# GeniusBottom.net
KiCad netlist of a schematic drawn in EAGLE
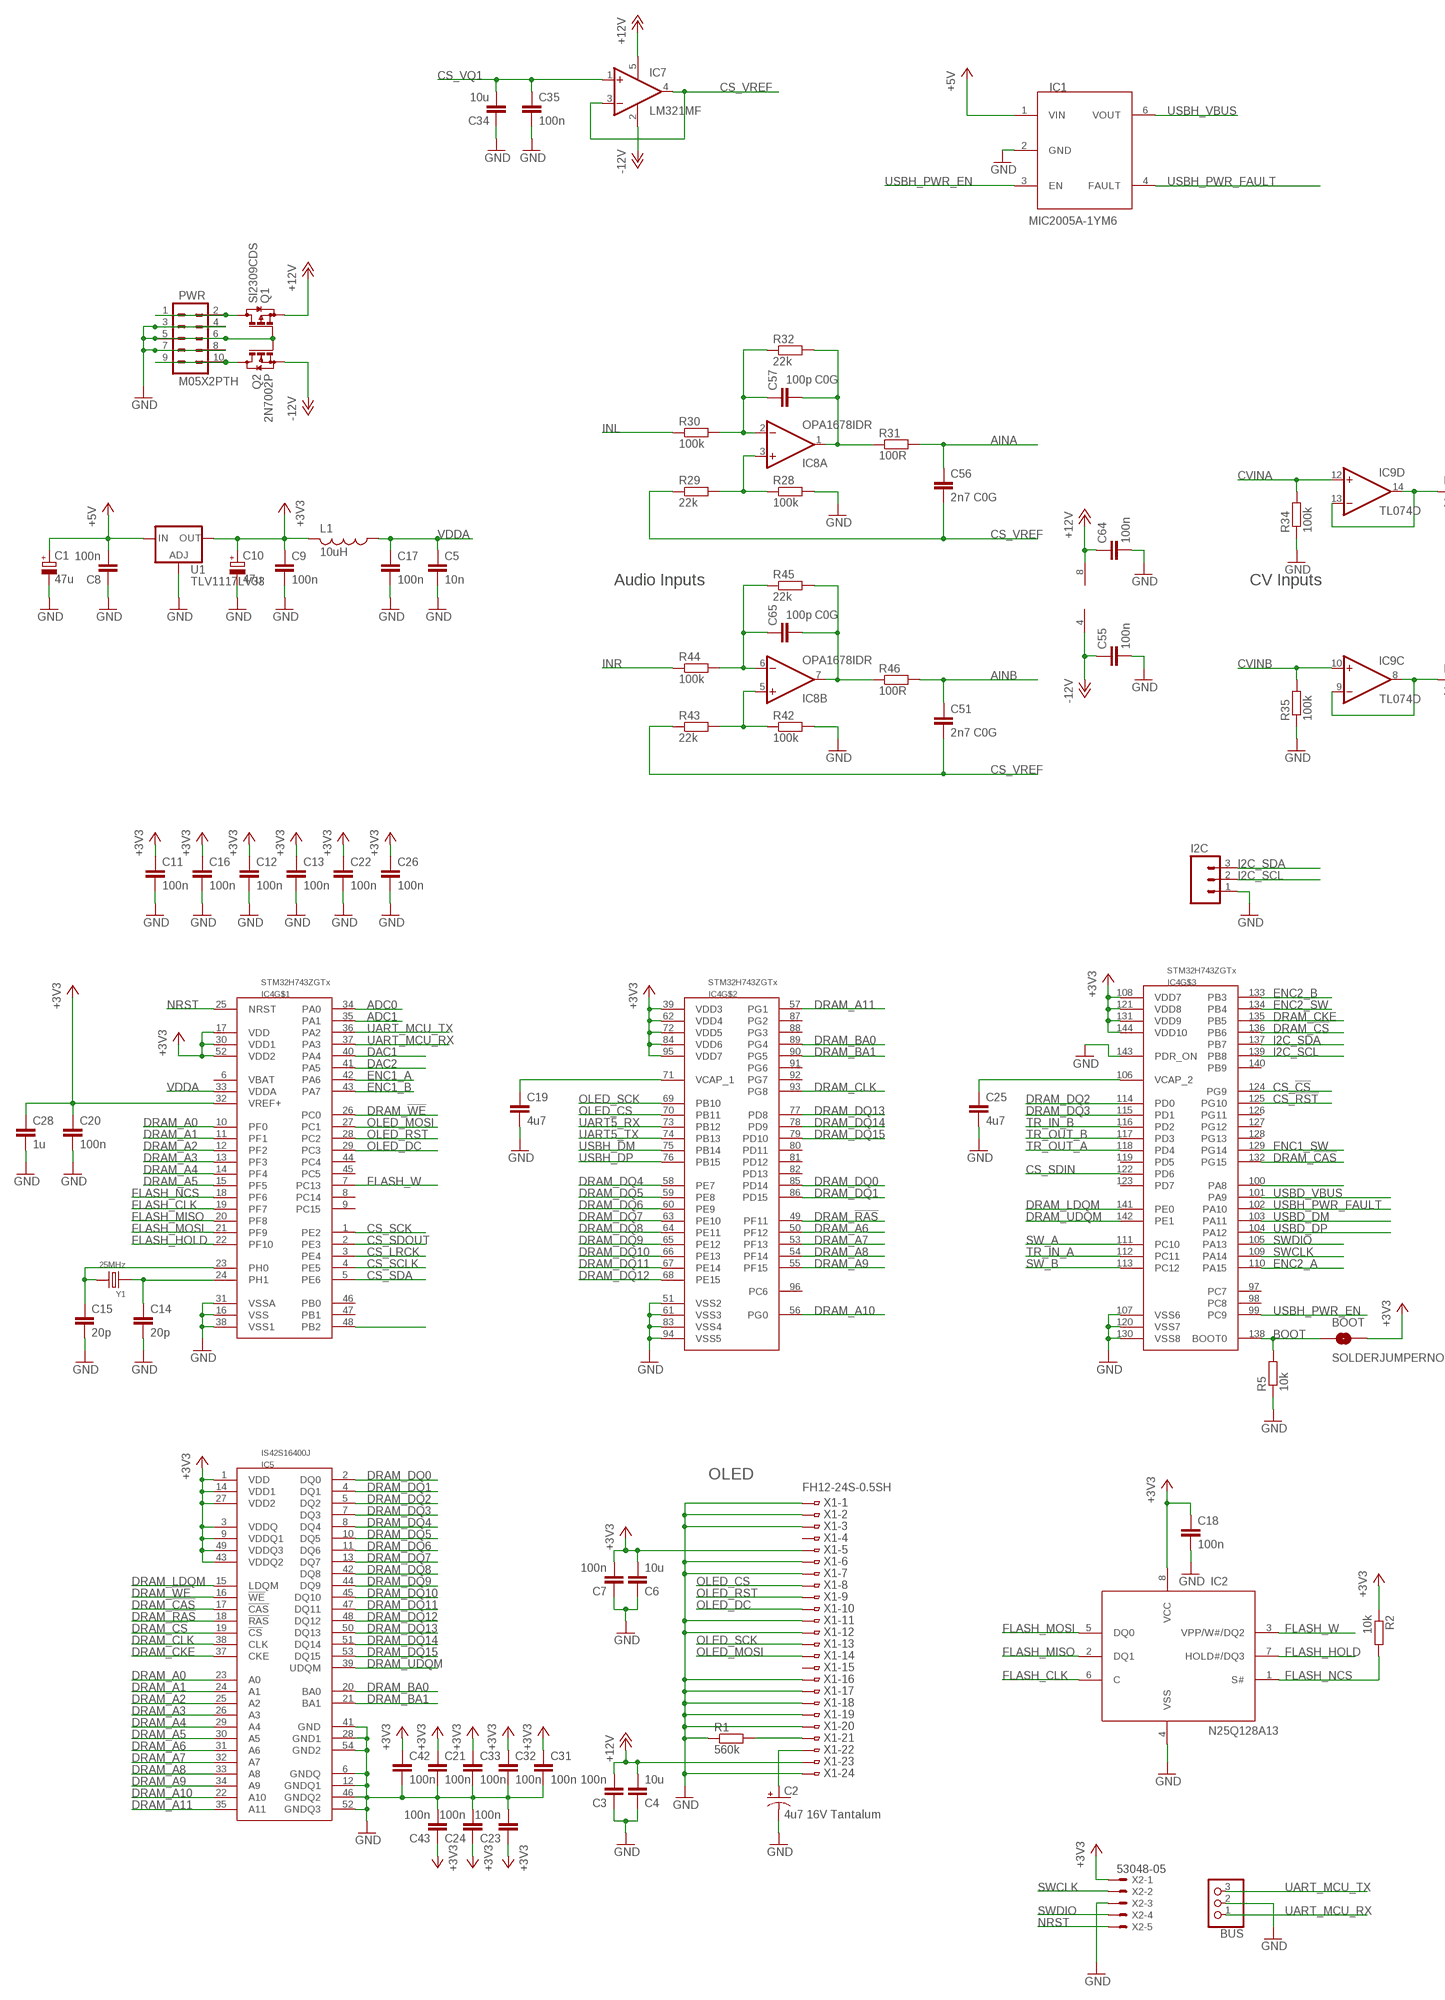
[diagram p0: schematic, sheet 1, part 1 of 2]
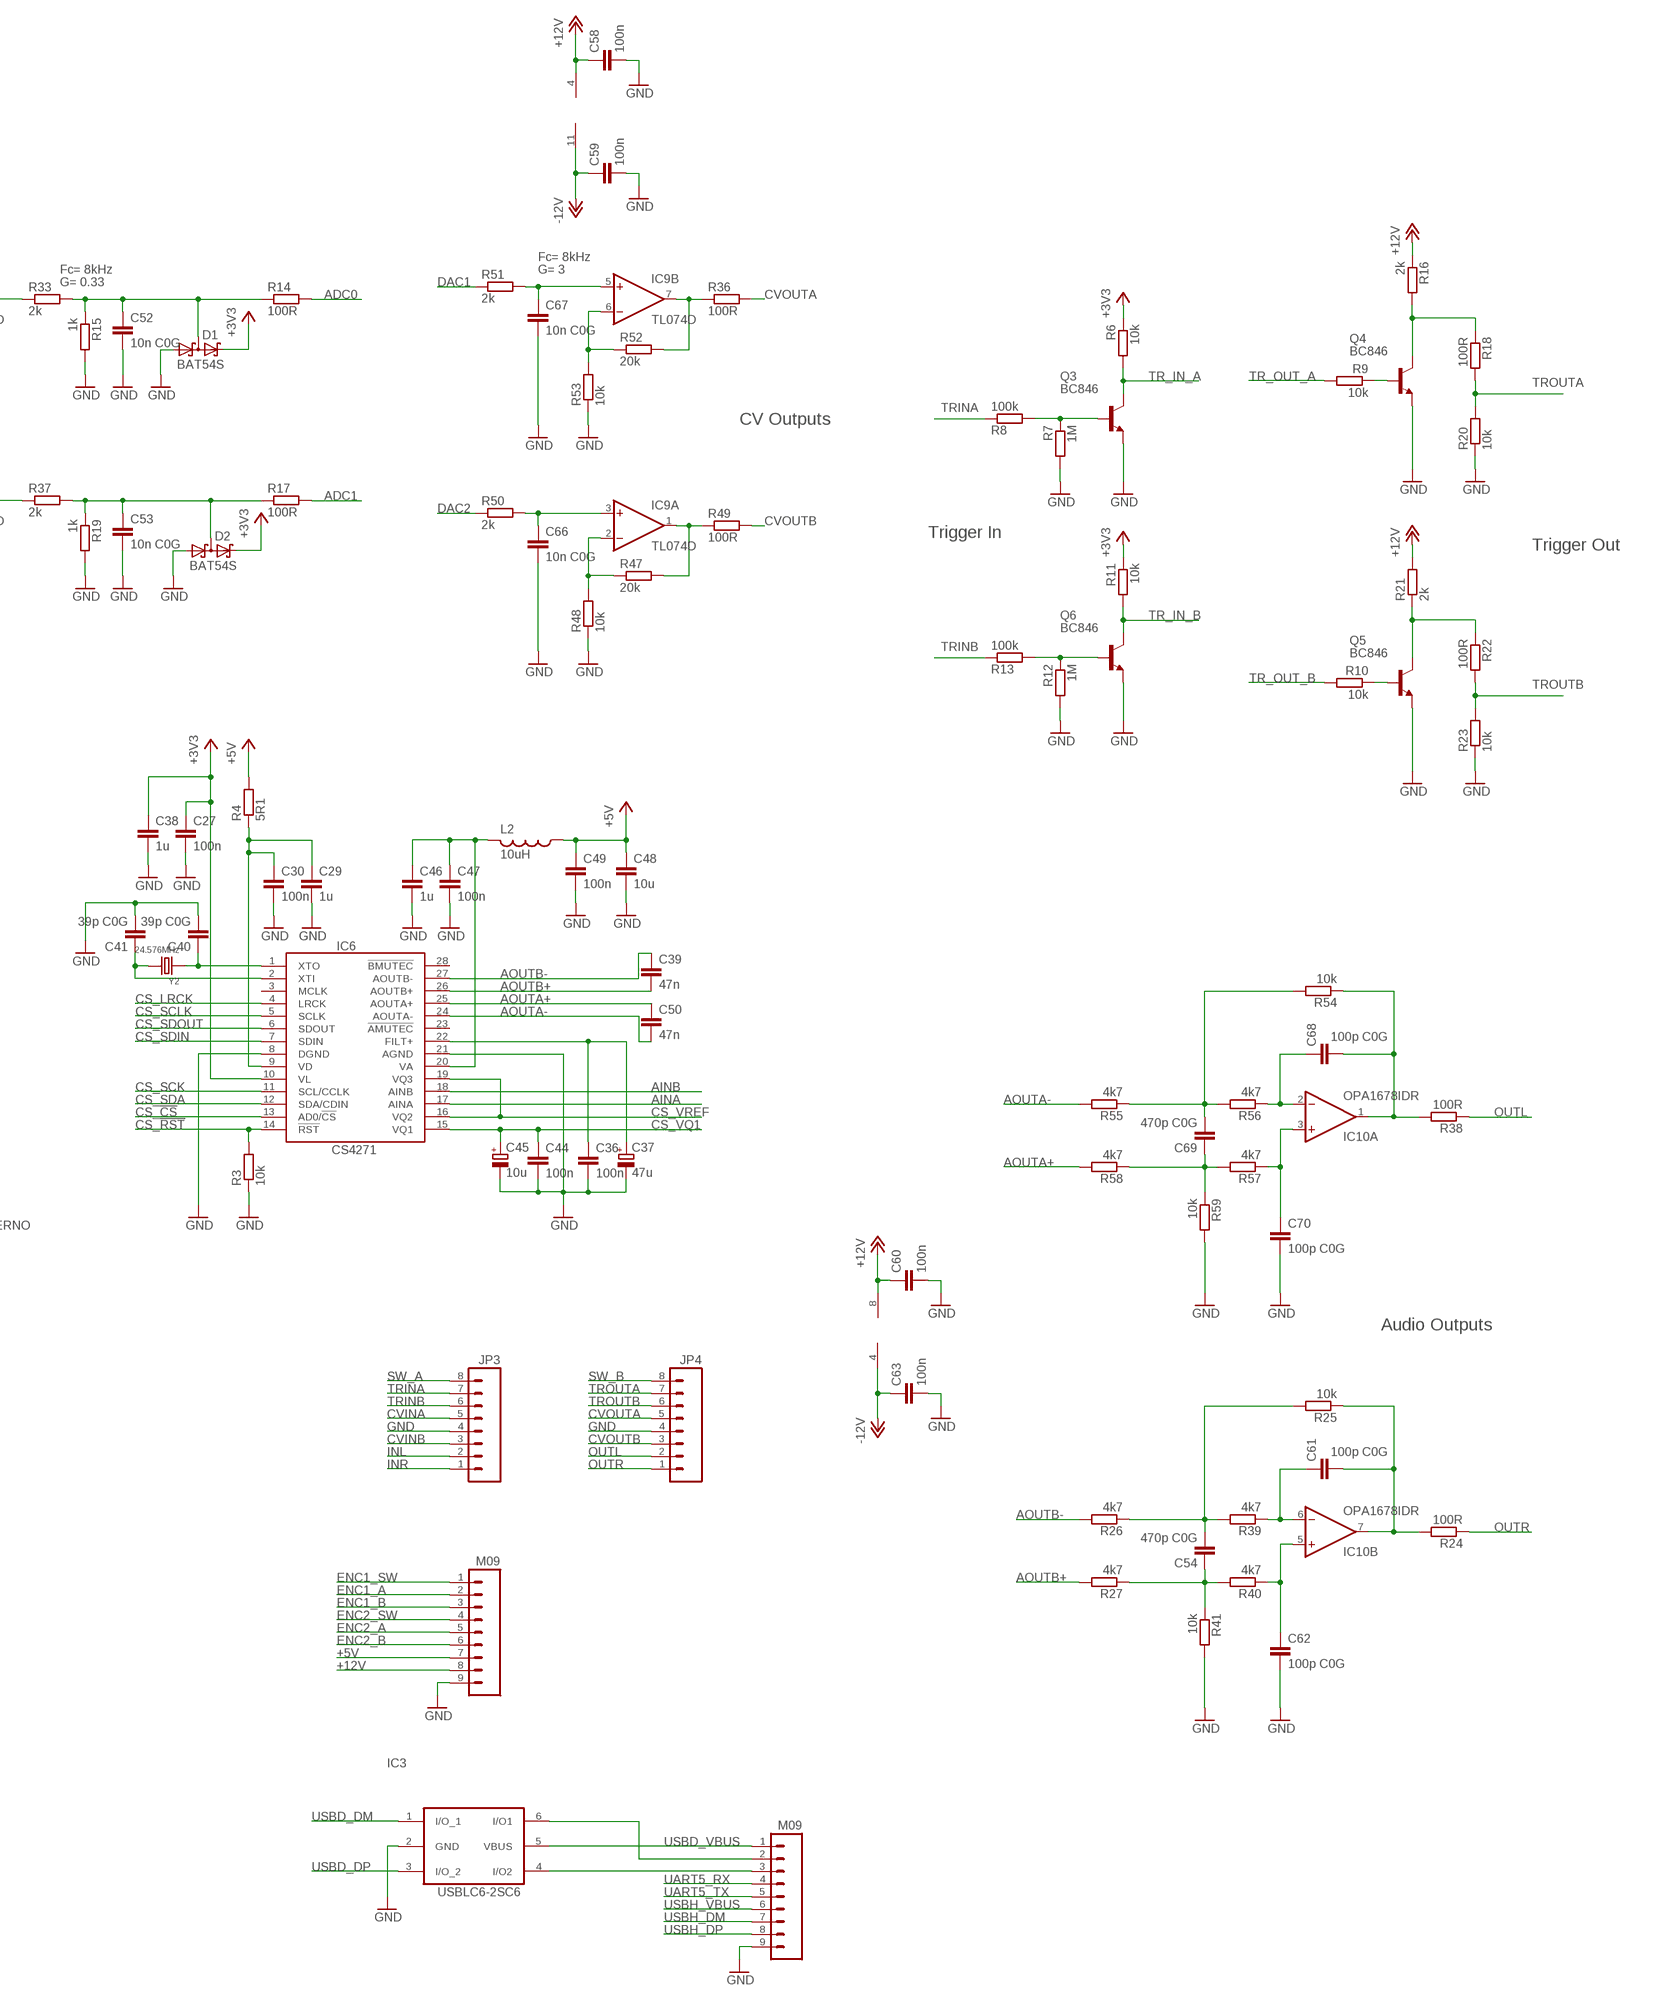
[diagram p1: schematic, sheet 1, part 2 of 2]

(export (version "E")
  (design (tool "Eeschema 10.0.6"))
  (components
    (comp (ref "BOOT")
      (value "SOLDERJUMPERNO")
      (footprint "eagle-import:SJ_2S-NO")
      (libsource (lib "eagle-import") (part "SOLDERJUMPERNO"))
    )
    (comp (ref "BUS")
      (value "CON-JST-1X03PH-TH")
      (footprint "eagle-import:JST-B3B-PH-KL")
      (libsource (lib "eagle-import") (part "CON-JST-1X03PH-TH"))
    )
    (comp (ref "C1")
      (value "47u")
      (footprint "eagle-import:CPOL-5")
      (libsource (lib "eagle-import") (part "CPOL-EU153CLV-0505"))
    )
    (comp (ref "C2")
      (value "4u7 16V Tantalum")
      (footprint "eagle-import:EIA3216")
      (libsource (lib "eagle-import") (part "CAP_POL1206"))
    )
    (comp (ref "C3")
      (value "100n")
      (footprint "eagle-import:C0603")
      (libsource (lib "eagle-import") (part "C-EUC0603"))
    )
    (comp (ref "C4")
      (value "10u")
      (footprint "eagle-import:C1206")
      (libsource (lib "eagle-import") (part "C-EUC1206"))
    )
    (comp (ref "C5")
      (value "10n")
      (footprint "eagle-import:C0603")
      (libsource (lib "eagle-import") (part "C-EUC0603"))
    )
    (comp (ref "C6")
      (value "10u")
      (footprint "eagle-import:C1206")
      (libsource (lib "eagle-import") (part "C-EUC1206"))
    )
    (comp (ref "C7")
      (value "100n")
      (footprint "eagle-import:C0603")
      (libsource (lib "eagle-import") (part "C-EUC0603"))
    )
    (comp (ref "C8")
      (value "100n")
      (footprint "eagle-import:C0603")
      (libsource (lib "eagle-import") (part "C-EUC0603"))
    )
    (comp (ref "C9")
      (value "100n")
      (footprint "eagle-import:C0603")
      (libsource (lib "eagle-import") (part "C-EUC0603"))
    )
    (comp (ref "C10")
      (value "47u")
      (footprint "eagle-import:CPOL-5")
      (libsource (lib "eagle-import") (part "CPOL-EU153CLV-0505"))
    )
    (comp (ref "C11")
      (value "100n")
      (footprint "eagle-import:C0603")
      (libsource (lib "eagle-import") (part "C-EUC0603"))
    )
    (comp (ref "C12")
      (value "100n")
      (footprint "eagle-import:C0603")
      (libsource (lib "eagle-import") (part "C-EUC0603"))
    )
    (comp (ref "C13")
      (value "100n")
      (footprint "eagle-import:C0603")
      (libsource (lib "eagle-import") (part "C-EUC0603"))
    )
    (comp (ref "C14")
      (value "20p")
      (footprint "eagle-import:C0603")
      (libsource (lib "eagle-import") (part "C-EUC0603"))
    )
    (comp (ref "C15")
      (value "20p")
      (footprint "eagle-import:C0603")
      (libsource (lib "eagle-import") (part "C-EUC0603"))
    )
    (comp (ref "C16")
      (value "100n")
      (footprint "eagle-import:C0603")
      (libsource (lib "eagle-import") (part "C-EUC0603"))
    )
    (comp (ref "C17")
      (value "100n")
      (footprint "eagle-import:C0603")
      (libsource (lib "eagle-import") (part "C-EUC0603"))
    )
    (comp (ref "C18")
      (value "100n")
      (footprint "eagle-import:C0603")
      (libsource (lib "eagle-import") (part "C-EUC0603"))
    )
    (comp (ref "C19")
      (value "4u7")
      (footprint "eagle-import:C0603")
      (libsource (lib "eagle-import") (part "C-EUC0603"))
    )
    (comp (ref "C20")
      (value "100n")
      (footprint "eagle-import:C0603")
      (libsource (lib "eagle-import") (part "C-EUC0603"))
    )
    (comp (ref "C21")
      (value "100n")
      (footprint "eagle-import:C0603")
      (libsource (lib "eagle-import") (part "C-EUC0603"))
    )
    (comp (ref "C22")
      (value "100n")
      (footprint "eagle-import:C0603")
      (libsource (lib "eagle-import") (part "C-EUC0603"))
    )
    (comp (ref "C23")
      (value "100n")
      (footprint "eagle-import:C0603")
      (libsource (lib "eagle-import") (part "C-EUC0603"))
    )
    (comp (ref "C24")
      (value "100n")
      (footprint "eagle-import:C0603")
      (libsource (lib "eagle-import") (part "C-EUC0603"))
    )
    (comp (ref "C25")
      (value "4u7")
      (footprint "eagle-import:C0603")
      (libsource (lib "eagle-import") (part "C-EUC0603"))
    )
    (comp (ref "C26")
      (value "100n")
      (footprint "eagle-import:C0603")
      (libsource (lib "eagle-import") (part "C-EUC0603"))
    )
    (comp (ref "C27")
      (value "100n")
      (footprint "eagle-import:C0603")
      (libsource (lib "eagle-import") (part "C-EUC0603"))
    )
    (comp (ref "C28")
      (value "1u")
      (footprint "eagle-import:C0603")
      (libsource (lib "eagle-import") (part "C-EUC0603"))
    )
    (comp (ref "C29")
      (value "1u")
      (footprint "eagle-import:C0603")
      (libsource (lib "eagle-import") (part "C-EUC0603"))
    )
    (comp (ref "C30")
      (value "100n")
      (footprint "eagle-import:C0603")
      (libsource (lib "eagle-import") (part "C-EUC0603"))
    )
    (comp (ref "C31")
      (value "100n")
      (footprint "eagle-import:C0603")
      (libsource (lib "eagle-import") (part "C-EUC0603"))
    )
    (comp (ref "C32")
      (value "100n")
      (footprint "eagle-import:C0603")
      (libsource (lib "eagle-import") (part "C-EUC0603"))
    )
    (comp (ref "C33")
      (value "100n")
      (footprint "eagle-import:C0603")
      (libsource (lib "eagle-import") (part "C-EUC0603"))
    )
    (comp (ref "C34")
      (value "10u")
      (footprint "eagle-import:C1206")
      (libsource (lib "eagle-import") (part "C-EUC1206"))
    )
    (comp (ref "C35")
      (value "100n")
      (footprint "eagle-import:C0603")
      (libsource (lib "eagle-import") (part "C-EUC0603"))
    )
    (comp (ref "C36")
      (value "100n")
      (footprint "eagle-import:C0603")
      (libsource (lib "eagle-import") (part "C-EUC0603"))
    )
    (comp (ref "C37")
      (value "47u")
      (footprint "eagle-import:CPOL-5")
      (libsource (lib "eagle-import") (part "CPOL-EU153CLV-0505"))
    )
    (comp (ref "C38")
      (value "1u")
      (footprint "eagle-import:C0603")
      (libsource (lib "eagle-import") (part "C-EUC0603"))
    )
    (comp (ref "C39")
      (value "47n")
      (footprint "eagle-import:C0603")
      (libsource (lib "eagle-import") (part "C-EUC0603"))
    )
    (comp (ref "C40")
      (value "39p C0G")
      (footprint "eagle-import:C0603")
      (libsource (lib "eagle-import") (part "C-EUC0603"))
    )
    (comp (ref "C41")
      (value "39p C0G")
      (footprint "eagle-import:C0603")
      (libsource (lib "eagle-import") (part "C-EUC0603"))
    )
    (comp (ref "C42")
      (value "100n")
      (footprint "eagle-import:C0603")
      (libsource (lib "eagle-import") (part "C-EUC0603"))
    )
    (comp (ref "C43")
      (value "100n")
      (footprint "eagle-import:C0603")
      (libsource (lib "eagle-import") (part "C-EUC0603"))
    )
    (comp (ref "C44")
      (value "100n")
      (footprint "eagle-import:C0603")
      (libsource (lib "eagle-import") (part "C-EUC0603"))
    )
    (comp (ref "C45")
      (value "10u")
      (footprint "eagle-import:CPOL-5")
      (libsource (lib "eagle-import") (part "CPOL-EU153CLV-0505"))
    )
    (comp (ref "C46")
      (value "1u")
      (footprint "eagle-import:C0603")
      (libsource (lib "eagle-import") (part "C-EUC0603"))
    )
    (comp (ref "C47")
      (value "100n")
      (footprint "eagle-import:C0603")
      (libsource (lib "eagle-import") (part "C-EUC0603"))
    )
    (comp (ref "C48")
      (value "10u")
      (footprint "eagle-import:C1206")
      (libsource (lib "eagle-import") (part "C-EUC1206"))
    )
    (comp (ref "C49")
      (value "100n")
      (footprint "eagle-import:C0603")
      (libsource (lib "eagle-import") (part "C-EUC0603"))
    )
    (comp (ref "C50")
      (value "47n")
      (footprint "eagle-import:C0603")
      (libsource (lib "eagle-import") (part "C-EUC0603"))
    )
    (comp (ref "C51")
      (value "2n7 C0G")
      (footprint "eagle-import:C0603")
      (libsource (lib "eagle-import") (part "C-EUC0603"))
    )
    (comp (ref "C52")
      (value "10n C0G")
      (footprint "eagle-import:C0603")
      (libsource (lib "eagle-import") (part "C-EUC0603"))
    )
    (comp (ref "C53")
      (value "10n C0G")
      (footprint "eagle-import:C0603")
      (libsource (lib "eagle-import") (part "C-EUC0603"))
    )
    (comp (ref "C54")
      (value "470p C0G")
      (footprint "eagle-import:C0603")
      (libsource (lib "eagle-import") (part "C-EUC0603"))
    )
    (comp (ref "C55")
      (value "100n")
      (footprint "eagle-import:C0603")
      (libsource (lib "eagle-import") (part "C-EUC0603"))
    )
    (comp (ref "C56")
      (value "2n7 C0G")
      (footprint "eagle-import:C0603")
      (libsource (lib "eagle-import") (part "C-EUC0603"))
    )
    (comp (ref "C57")
      (value "100p C0G")
      (footprint "eagle-import:C0603")
      (libsource (lib "eagle-import") (part "C-EUC0603"))
    )
    (comp (ref "C58")
      (value "100n")
      (footprint "eagle-import:C0603")
      (libsource (lib "eagle-import") (part "C-EUC0603"))
    )
    (comp (ref "C59")
      (value "100n")
      (footprint "eagle-import:C0603")
      (libsource (lib "eagle-import") (part "C-EUC0603"))
    )
    (comp (ref "C60")
      (value "100n")
      (footprint "eagle-import:C0603")
      (libsource (lib "eagle-import") (part "C-EUC0603"))
    )
    (comp (ref "C61")
      (value "100p C0G")
      (footprint "eagle-import:C0603")
      (libsource (lib "eagle-import") (part "C-EUC0603"))
    )
    (comp (ref "C62")
      (value "100p C0G")
      (footprint "eagle-import:C0603")
      (libsource (lib "eagle-import") (part "C-EUC0603"))
    )
    (comp (ref "C63")
      (value "100n")
      (footprint "eagle-import:C0603")
      (libsource (lib "eagle-import") (part "C-EUC0603"))
    )
    (comp (ref "C64")
      (value "100n")
      (footprint "eagle-import:C0603")
      (libsource (lib "eagle-import") (part "C-EUC0603"))
    )
    (comp (ref "C65")
      (value "100p C0G")
      (footprint "eagle-import:C0603")
      (libsource (lib "eagle-import") (part "C-EUC0603"))
    )
    (comp (ref "C66")
      (value "10n C0G")
      (footprint "eagle-import:C0603")
      (libsource (lib "eagle-import") (part "C-EUC0603"))
    )
    (comp (ref "C67")
      (value "10n C0G")
      (footprint "eagle-import:C0603")
      (libsource (lib "eagle-import") (part "C-EUC0603"))
    )
    (comp (ref "C68")
      (value "100p C0G")
      (footprint "eagle-import:C0603")
      (libsource (lib "eagle-import") (part "C-EUC0603"))
    )
    (comp (ref "C69")
      (value "470p C0G")
      (footprint "eagle-import:C0603")
      (libsource (lib "eagle-import") (part "C-EUC0603"))
    )
    (comp (ref "C70")
      (value "100p C0G")
      (footprint "eagle-import:C0603")
      (libsource (lib "eagle-import") (part "C-EUC0603"))
    )
    (comp (ref "D1")
      (value "BAT54S")
      (footprint "eagle-import:SOT23")
      (libsource (lib "eagle-import") (part "BAT54S"))
    )
    (comp (ref "D2")
      (value "BAT54S")
      (footprint "eagle-import:SOT23")
      (libsource (lib "eagle-import") (part "BAT54S"))
    )
    (comp (ref "I2C")
      (value "M03PTH")
      (footprint "eagle-import:1X03")
      (libsource (lib "eagle-import") (part "M03PTH"))
    )
    (comp (ref "IC1")
      (value "MIC2005A-1YM6")
      (footprint "eagle-import:SOT23-6")
      (libsource (lib "eagle-import") (part "MIC2005"))
    )
    (comp (ref "IC2")
      (value "N25Q128A13")
      (footprint "eagle-import:SO8W")
      (libsource (lib "eagle-import") (part "N25Q128A13"))
    )
    (comp (ref "IC3")
      (value "USBLC6-2SC6")
      (footprint "eagle-import:SOT-23-6L")
      (libsource (lib "eagle-import") (part "USBLC6-2SC6"))
    )
    (comp (ref "IC4")
      (value "STM32H743ZGTx")
      (footprint "eagle-import:QFP50P2200X2200X160-144N")
      (fields (field (name "OC_FARNELL") "2484975"))
      (libsource (lib "eagle-import") (part "STM32F42XZ/43XZ(144PIN)LQFP144"))
    )
    (comp (ref "IC5")
      (value "IS42S16400J")
      (footprint "eagle-import:TSOP54-400")
      (libsource (lib "eagle-import") (part "IS42S16400J"))
    )
    (comp (ref "IC6")
      (value "CS4271")
      (footprint "eagle-import:TSSOP28-0.65-9.7X4.4MM")
      (libsource (lib "eagle-import") (part "CS4271"))
    )
    (comp (ref "IC7")
      (value "LM321MF")
      (footprint "eagle-import:SOT23-5")
      (libsource (lib "eagle-import") (part "LM321?MF"))
    )
    (comp (ref "IC8")
      (value "OPA1678IDR")
      (footprint "eagle-import:SO08")
      (libsource (lib "eagle-import") (part "NE5532D"))
    )
    (comp (ref "IC9")
      (value "TL074D")
      (footprint "eagle-import:SO14")
      (libsource (lib "eagle-import") (part "TL074D"))
    )
    (comp (ref "IC10")
      (value "OPA1678IDR")
      (footprint "eagle-import:SO08")
      (libsource (lib "eagle-import") (part "NE5532D"))
    )
    (comp (ref "JP1")
      (value "M09")
      (footprint "eagle-import:1X09")
      (libsource (lib "eagle-import") (part "M09"))
    )
    (comp (ref "JP2")
      (value "M09")
      (footprint "eagle-import:1X09")
      (libsource (lib "eagle-import") (part "M09"))
    )
    (comp (ref "JP3")
      (value "M081X08")
      (footprint "eagle-import:1X08")
      (libsource (lib "eagle-import") (part "M081X08"))
    )
    (comp (ref "JP4")
      (value "M081X08")
      (footprint "eagle-import:1X08")
      (libsource (lib "eagle-import") (part "M081X08"))
    )
    (comp (ref "L1")
      (value "10uH")
      (footprint "eagle-import:0603")
      (libsource (lib "eagle-import") (part "INDUCTOR"))
    )
    (comp (ref "L2")
      (value "10uH")
      (footprint "eagle-import:0603")
      (libsource (lib "eagle-import") (part "INDUCTOR"))
    )
    (comp (ref "PWR")
      (value "M05X2PTH")
      (footprint "eagle-import:AVR_ICSP")
      (libsource (lib "eagle-import") (part "M05X2PTH"))
    )
    (comp (ref "Q1")
      (value "SI2309CDS")
      (footprint "eagle-import:SOT23")
      (libsource (lib "eagle-import") (part "BSS84"))
    )
    (comp (ref "Q2")
      (value "2N7002P")
      (footprint "eagle-import:SOT23")
      (libsource (lib "eagle-import") (part "BSS123"))
    )
    (comp (ref "Q3")
      (value "BC846")
      (footprint "eagle-import:SOT23")
      (libsource (lib "eagle-import") (part "BC846"))
    )
    (comp (ref "Q4")
      (value "BC846")
      (footprint "eagle-import:SOT23")
      (libsource (lib "eagle-import") (part "BC846"))
    )
    (comp (ref "Q5")
      (value "BC846")
      (footprint "eagle-import:SOT23")
      (libsource (lib "eagle-import") (part "BC846"))
    )
    (comp (ref "Q6")
      (value "BC846")
      (footprint "eagle-import:SOT23")
      (libsource (lib "eagle-import") (part "BC846"))
    )
    (comp (ref "R1")
      (value "560k")
      (footprint "eagle-import:0603")
      (libsource (lib "eagle-import") (part "R-EU_0603"))
    )
    (comp (ref "R2")
      (value "10k")
      (footprint "eagle-import:0603")
      (libsource (lib "eagle-import") (part "R-EU_0603"))
    )
    (comp (ref "R3")
      (value "10k")
      (footprint "eagle-import:0603")
      (libsource (lib "eagle-import") (part "R-EU_0603"))
    )
    (comp (ref "R4")
      (value "5R1")
      (footprint "eagle-import:0603")
      (libsource (lib "eagle-import") (part "R-EU_0603"))
    )
    (comp (ref "R5")
      (value "10k")
      (footprint "eagle-import:0603")
      (libsource (lib "eagle-import") (part "R-EU_0603"))
    )
    (comp (ref "R6")
      (value "10k")
      (footprint "eagle-import:0603")
      (libsource (lib "eagle-import") (part "R-EU_0603"))
    )
    (comp (ref "R7")
      (value "1M")
      (footprint "eagle-import:0603")
      (libsource (lib "eagle-import") (part "R-EU_0603"))
    )
    (comp (ref "R8")
      (value "100k")
      (footprint "eagle-import:0603")
      (libsource (lib "eagle-import") (part "R-EU_0603"))
    )
    (comp (ref "R9")
      (value "10k")
      (footprint "eagle-import:0603")
      (libsource (lib "eagle-import") (part "R-EU_0603"))
    )
    (comp (ref "R10")
      (value "10k")
      (footprint "eagle-import:0603")
      (libsource (lib "eagle-import") (part "R-EU_0603"))
    )
    (comp (ref "R11")
      (value "10k")
      (footprint "eagle-import:0603")
      (libsource (lib "eagle-import") (part "R-EU_0603"))
    )
    (comp (ref "R12")
      (value "1M")
      (footprint "eagle-import:0603")
      (libsource (lib "eagle-import") (part "R-EU_0603"))
    )
    (comp (ref "R13")
      (value "100k")
      (footprint "eagle-import:0603")
      (libsource (lib "eagle-import") (part "R-EU_0603"))
    )
    (comp (ref "R14")
      (value "100R")
      (footprint "eagle-import:0603")
      (libsource (lib "eagle-import") (part "R-EU_0603"))
    )
    (comp (ref "R15")
      (value "1k")
      (footprint "eagle-import:0603")
      (libsource (lib "eagle-import") (part "R-EU_0603"))
    )
    (comp (ref "R16")
      (value "2k")
      (footprint "eagle-import:0603")
      (libsource (lib "eagle-import") (part "R-EU_0603"))
    )
    (comp (ref "R17")
      (value "100R")
      (footprint "eagle-import:0603")
      (libsource (lib "eagle-import") (part "R-EU_0603"))
    )
    (comp (ref "R18")
      (value "100R")
      (footprint "eagle-import:0603")
      (libsource (lib "eagle-import") (part "R-EU_0603"))
    )
    (comp (ref "R19")
      (value "1k")
      (footprint "eagle-import:0603")
      (libsource (lib "eagle-import") (part "R-EU_0603"))
    )
    (comp (ref "R20")
      (value "10k")
      (footprint "eagle-import:0603")
      (libsource (lib "eagle-import") (part "R-EU_0603"))
    )
    (comp (ref "R21")
      (value "2k")
      (footprint "eagle-import:0603")
      (libsource (lib "eagle-import") (part "R-EU_0603"))
    )
    (comp (ref "R22")
      (value "100R")
      (footprint "eagle-import:0603")
      (libsource (lib "eagle-import") (part "R-EU_0603"))
    )
    (comp (ref "R23")
      (value "10k")
      (footprint "eagle-import:0603")
      (libsource (lib "eagle-import") (part "R-EU_0603"))
    )
    (comp (ref "R24")
      (value "100R")
      (footprint "eagle-import:0603")
      (libsource (lib "eagle-import") (part "R-EU_0603"))
    )
    (comp (ref "R25")
      (value "10k")
      (footprint "eagle-import:0603")
      (libsource (lib "eagle-import") (part "R-EU_0603"))
    )
    (comp (ref "R26")
      (value "4k7")
      (footprint "eagle-import:0603")
      (libsource (lib "eagle-import") (part "R-EU_0603"))
    )
    (comp (ref "R27")
      (value "4k7")
      (footprint "eagle-import:0603")
      (libsource (lib "eagle-import") (part "R-EU_0603"))
    )
    (comp (ref "R28")
      (value "100k")
      (footprint "eagle-import:0603")
      (libsource (lib "eagle-import") (part "R-EU_0603"))
    )
    (comp (ref "R29")
      (value "22k")
      (footprint "eagle-import:0603")
      (libsource (lib "eagle-import") (part "R-EU_0603"))
    )
    (comp (ref "R30")
      (value "100k")
      (footprint "eagle-import:0603")
      (libsource (lib "eagle-import") (part "R-EU_0603"))
    )
    (comp (ref "R31")
      (value "100R")
      (footprint "eagle-import:0603")
      (libsource (lib "eagle-import") (part "R-EU_0603"))
    )
    (comp (ref "R32")
      (value "22k")
      (footprint "eagle-import:0603")
      (libsource (lib "eagle-import") (part "R-EU_0603"))
    )
    (comp (ref "R33")
      (value "2k")
      (footprint "eagle-import:0603")
      (libsource (lib "eagle-import") (part "R-EU_0603"))
    )
    (comp (ref "R34")
      (value "100k")
      (footprint "eagle-import:0603")
      (libsource (lib "eagle-import") (part "R-EU_0603"))
    )
    (comp (ref "R35")
      (value "100k")
      (footprint "eagle-import:0603")
      (libsource (lib "eagle-import") (part "R-EU_0603"))
    )
    (comp (ref "R36")
      (value "100R")
      (footprint "eagle-import:0603")
      (libsource (lib "eagle-import") (part "R-EU_0603"))
    )
    (comp (ref "R37")
      (value "2k")
      (footprint "eagle-import:0603")
      (libsource (lib "eagle-import") (part "R-EU_0603"))
    )
    (comp (ref "R38")
      (value "100R")
      (footprint "eagle-import:0603")
      (libsource (lib "eagle-import") (part "R-EU_0603"))
    )
    (comp (ref "R39")
      (value "4k7")
      (footprint "eagle-import:0603")
      (libsource (lib "eagle-import") (part "R-EU_0603"))
    )
    (comp (ref "R40")
      (value "4k7")
      (footprint "eagle-import:0603")
      (libsource (lib "eagle-import") (part "R-EU_0603"))
    )
    (comp (ref "R41")
      (value "10k")
      (footprint "eagle-import:0603")
      (libsource (lib "eagle-import") (part "R-EU_0603"))
    )
    (comp (ref "R42")
      (value "100k")
      (footprint "eagle-import:0603")
      (libsource (lib "eagle-import") (part "R-EU_0603"))
    )
    (comp (ref "R43")
      (value "22k")
      (footprint "eagle-import:0603")
      (libsource (lib "eagle-import") (part "R-EU_0603"))
    )
    (comp (ref "R44")
      (value "100k")
      (footprint "eagle-import:0603")
      (libsource (lib "eagle-import") (part "R-EU_0603"))
    )
    (comp (ref "R45")
      (value "22k")
      (footprint "eagle-import:0603")
      (libsource (lib "eagle-import") (part "R-EU_0603"))
    )
    (comp (ref "R46")
      (value "100R")
      (footprint "eagle-import:0603")
      (libsource (lib "eagle-import") (part "R-EU_0603"))
    )
    (comp (ref "R47")
      (value "20k")
      (footprint "eagle-import:0603")
      (libsource (lib "eagle-import") (part "R-EU_0603"))
    )
    (comp (ref "R48")
      (value "10k")
      (footprint "eagle-import:0603")
      (libsource (lib "eagle-import") (part "R-EU_0603"))
    )
    (comp (ref "R49")
      (value "100R")
      (footprint "eagle-import:0603")
      (libsource (lib "eagle-import") (part "R-EU_0603"))
    )
    (comp (ref "R50")
      (value "2k")
      (footprint "eagle-import:0603")
      (libsource (lib "eagle-import") (part "R-EU_0603"))
    )
    (comp (ref "R51")
      (value "2k")
      (footprint "eagle-import:0603")
      (libsource (lib "eagle-import") (part "R-EU_0603"))
    )
    (comp (ref "R52")
      (value "20k")
      (footprint "eagle-import:0603")
      (libsource (lib "eagle-import") (part "R-EU_0603"))
    )
    (comp (ref "R53")
      (value "10k")
      (footprint "eagle-import:0603")
      (libsource (lib "eagle-import") (part "R-EU_0603"))
    )
    (comp (ref "R54")
      (value "10k")
      (footprint "eagle-import:0603")
      (libsource (lib "eagle-import") (part "R-EU_0603"))
    )
    (comp (ref "R55")
      (value "4k7")
      (footprint "eagle-import:0603")
      (libsource (lib "eagle-import") (part "R-EU_0603"))
    )
    (comp (ref "R56")
      (value "4k7")
      (footprint "eagle-import:0603")
      (libsource (lib "eagle-import") (part "R-EU_0603"))
    )
    (comp (ref "R57")
      (value "4k7")
      (footprint "eagle-import:0603")
      (libsource (lib "eagle-import") (part "R-EU_0603"))
    )
    (comp (ref "R58")
      (value "4k7")
      (footprint "eagle-import:0603")
      (libsource (lib "eagle-import") (part "R-EU_0603"))
    )
    (comp (ref "R59")
      (value "10k")
      (footprint "eagle-import:0603")
      (libsource (lib "eagle-import") (part "R-EU_0603"))
    )
    (comp (ref "U1")
      (value "TLV1117LV33")
      (footprint "eagle-import:SOT223")
      (libsource (lib "eagle-import") (part "LD117A?S33TR"))
    )
    (comp (ref "X1")
      (value "FH12-24S-0.5SH")
      (footprint "eagle-import:FH12-24S-0.5SH")
      (fields (field (name "MPN") "FH12-24S-0.5SH(55)"))
      (libsource (lib "eagle-import") (part "FH12-24S-0.5SH"))
    )
    (comp (ref "X2")
      (value "53048-05")
      (footprint "eagle-import:53048-05")
      (fields (field (name "MF") "MOLEX") (field (name "MPN") "53048-0510"))
      (libsource (lib "eagle-import") (part "53?-05048"))
    )
    (comp (ref "Y1")
      (value "25MHz")
      (footprint "eagle-import:X2-SMD-5.0X3.2X1.3MM")
      (fields (field (name "MPN") "5032/2P"))
      (libsource (lib "eagle-import") (part "SMD-CRYSTAL-8MHZ-20PF-20PPM(2P-5.0X3.2MM)"))
    )
    (comp (ref "Y2")
      (value "24.576MHz")
      (footprint "eagle-import:X2-SMD-5.0X3.2X1.3MM")
      (fields (field (name "MPN") "5032/2P"))
      (libsource (lib "eagle-import") (part "SMD-CRYSTAL-8MHZ-20PF-20PPM(2P-5.0X3.2MM)"))
    )
  )
  (nets
    (net (code "1") (name "+3V3") (class "Default")
      (node (ref "BOOT") (pin "2") (pinfunction "2_2") (pintype "passive"))
      (node (ref "C10") (pin "+") (pinfunction "+_+") (pintype "passive"))
      (node (ref "C11") (pin "1") (pinfunction "1_1") (pintype "passive"))
      (node (ref "C12") (pin "1") (pinfunction "1_1") (pintype "passive"))
      (node (ref "C13") (pin "1") (pinfunction "1_1") (pintype "passive"))
      (node (ref "C16") (pin "1") (pinfunction "1_1") (pintype "passive"))
      (node (ref "C18") (pin "1") (pinfunction "1_1") (pintype "passive"))
      (node (ref "C20") (pin "1") (pinfunction "1_1") (pintype "passive"))
      (node (ref "C21") (pin "1") (pinfunction "1_1") (pintype "passive"))
      (node (ref "C22") (pin "1") (pinfunction "1_1") (pintype "passive"))
      (node (ref "C23") (pin "1") (pinfunction "1_1") (pintype "passive"))
      (node (ref "C24") (pin "1") (pinfunction "1_1") (pintype "passive"))
      (node (ref "C26") (pin "1") (pinfunction "1_1") (pintype "passive"))
      (node (ref "C27") (pin "1") (pinfunction "1_1") (pintype "passive"))
      (node (ref "C28") (pin "1") (pinfunction "1_1") (pintype "passive"))
      (node (ref "C31") (pin "1") (pinfunction "1_1") (pintype "passive"))
      (node (ref "C32") (pin "1") (pinfunction "1_1") (pintype "passive"))
      (node (ref "C33") (pin "1") (pinfunction "1_1") (pintype "passive"))
      (node (ref "C38") (pin "1") (pinfunction "1_1") (pintype "passive"))
      (node (ref "C42") (pin "1") (pinfunction "1_1") (pintype "passive"))
      (node (ref "C43") (pin "1") (pinfunction "1_1") (pintype "passive"))
      (node (ref "C6") (pin "2") (pinfunction "2_2") (pintype "passive"))
      (node (ref "C7") (pin "2") (pinfunction "2_2") (pintype "passive"))
      (node (ref "C9") (pin "1") (pinfunction "1_1") (pintype "passive"))
      (node (ref "D1") (pin "2") (pinfunction "C2_2") (pintype "passive"))
      (node (ref "D2") (pin "2") (pinfunction "C2_2") (pintype "passive"))
      (node (ref "IC2") (pin "8") (pinfunction "VCC_8") (pintype "bidirectional"))
      (node (ref "IC4") (pin "108") (pinfunction "VDD7_108") (pintype "bidirectional"))
      (node (ref "IC4") (pin "121") (pinfunction "VDD8_121") (pintype "bidirectional"))
      (node (ref "IC4") (pin "131") (pinfunction "VDD9_131") (pintype "bidirectional"))
      (node (ref "IC4") (pin "144") (pinfunction "VDD10_144") (pintype "bidirectional"))
      (node (ref "IC4") (pin "17") (pinfunction "VDD_17") (pintype "bidirectional"))
      (node (ref "IC4") (pin "30") (pinfunction "VDD1_30") (pintype "bidirectional"))
      (node (ref "IC4") (pin "32") (pinfunction "VREF+_32") (pintype "bidirectional"))
      (node (ref "IC4") (pin "39") (pinfunction "VDD3_39") (pintype "bidirectional"))
      (node (ref "IC4") (pin "52") (pinfunction "VDD2_52") (pintype "bidirectional"))
      (node (ref "IC4") (pin "62") (pinfunction "VDD4_62") (pintype "bidirectional"))
      (node (ref "IC4") (pin "72") (pinfunction "VDD5_72") (pintype "bidirectional"))
      (node (ref "IC4") (pin "84") (pinfunction "VDD6_84") (pintype "bidirectional"))
      (node (ref "IC4") (pin "95") (pinfunction "VDD7_95") (pintype "bidirectional"))
      (node (ref "IC5") (pin "1") (pinfunction "VDD_1") (pintype "bidirectional"))
      (node (ref "IC5") (pin "14") (pinfunction "VDD1_14") (pintype "bidirectional"))
      (node (ref "IC5") (pin "27") (pinfunction "VDD2_27") (pintype "bidirectional"))
      (node (ref "IC5") (pin "3") (pinfunction "VDDQ_3") (pintype "bidirectional"))
      (node (ref "IC5") (pin "43") (pinfunction "VDDQ2_43") (pintype "bidirectional"))
      (node (ref "IC5") (pin "49") (pinfunction "VDDQ3_49") (pintype "bidirectional"))
      (node (ref "IC5") (pin "9") (pinfunction "VDDQ1_9") (pintype "bidirectional"))
      (node (ref "IC6") (pin "10") (pinfunction "VL_10") (pintype "bidirectional"))
      (node (ref "L1") (pin "2") (pinfunction "2_2") (pintype "passive"))
      (node (ref "R11") (pin "1") (pinfunction "1_1") (pintype "passive"))
      (node (ref "R2") (pin "1") (pinfunction "1_1") (pintype "passive"))
      (node (ref "R6") (pin "1") (pinfunction "1_1") (pintype "passive"))
      (node (ref "U1") (pin "4") (pinfunction "OUT_4") (pintype "passive"))
      (node (ref "X1") (pin "5") (pinfunction "1_5") (pintype "passive"))
      (node (ref "X2") (pin "1") (pinfunction "S_1") (pintype "passive"))
    )
    (net (code "2") (name "+5V") (class "Default")
      (node (ref "C1") (pin "+") (pinfunction "+_+") (pintype "passive"))
      (node (ref "C48") (pin "1") (pinfunction "1_1") (pintype "passive"))
      (node (ref "C49") (pin "1") (pinfunction "1_1") (pintype "passive"))
      (node (ref "C8") (pin "2") (pinfunction "2_2") (pintype "passive"))
      (node (ref "IC1") (pin "1") (pinfunction "VIN_1") (pintype "power_in"))
      (node (ref "JP2") (pin "7") (pinfunction "7_7") (pintype "passive"))
      (node (ref "L2") (pin "1") (pinfunction "1_1") (pintype "passive"))
      (node (ref "R4") (pin "2") (pinfunction "2_2") (pintype "passive"))
      (node (ref "U1") (pin "3") (pinfunction "IN_3") (pintype "input"))
    )
    (net (code "3") (name "+12V") (class "Default")
      (node (ref "C3") (pin "2") (pinfunction "2_2") (pintype "passive"))
      (node (ref "C4") (pin "2") (pinfunction "2_2") (pintype "passive"))
      (node (ref "C58") (pin "1") (pinfunction "1_1") (pintype "passive"))
      (node (ref "C60") (pin "1") (pinfunction "1_1") (pintype "passive"))
      (node (ref "C64") (pin "1") (pinfunction "1_1") (pintype "passive"))
      (node (ref "IC10") (pin "8") (pinfunction "V+_8") (pintype "power_in"))
      (node (ref "IC7") (pin "5") (pinfunction "V+_5") (pintype "power_in"))
      (node (ref "IC8") (pin "8") (pinfunction "V+_8") (pintype "power_in"))
      (node (ref "IC9") (pin "4") (pinfunction "V+_4") (pintype "power_in"))
      (node (ref "JP2") (pin "8") (pinfunction "8_8") (pintype "passive"))
      (node (ref "Q1") (pin "2") (pinfunction "S_2") (pintype "passive"))
      (node (ref "R16") (pin "1") (pinfunction "1_1") (pintype "passive"))
      (node (ref "R21") (pin "2") (pinfunction "2_2") (pintype "passive"))
      (node (ref "X1") (pin "23") (pinfunction "1_23") (pintype "passive"))
    )
    (net (code "4") (name "-12V") (class "Default")
      (node (ref "C55") (pin "1") (pinfunction "1_1") (pintype "passive"))
      (node (ref "C59") (pin "1") (pinfunction "1_1") (pintype "passive"))
      (node (ref "C63") (pin "1") (pinfunction "1_1") (pintype "passive"))
      (node (ref "IC10") (pin "4") (pinfunction "V-_4") (pintype "power_in"))
      (node (ref "IC7") (pin "2") (pinfunction "V-_2") (pintype "power_in"))
      (node (ref "IC8") (pin "4") (pinfunction "V-_4") (pintype "power_in"))
      (node (ref "IC9") (pin "11") (pinfunction "V-_11") (pintype "power_in"))
      (node (ref "Q2") (pin "2") (pinfunction "S_2") (pintype "passive"))
    )
    (net (code "5") (name "/ADC0") (class "Default")
      (node (ref "IC4") (pin "34") (pinfunction "PA0_34") (pintype "bidirectional"))
      (node (ref "R14") (pin "2") (pinfunction "2_2") (pintype "passive"))
    )
    (net (code "6") (name "/ADC1") (class "Default")
      (node (ref "IC4") (pin "35") (pinfunction "PA1_35") (pintype "bidirectional"))
      (node (ref "R17") (pin "2") (pinfunction "2_2") (pintype "passive"))
    )
    (net (code "7") (name "/AINA") (class "Default")
      (node (ref "C56") (pin "1") (pinfunction "1_1") (pintype "passive"))
      (node (ref "IC6") (pin "17") (pinfunction "AINA_17") (pintype "bidirectional"))
      (node (ref "R31") (pin "2") (pinfunction "2_2") (pintype "passive"))
    )
    (net (code "8") (name "/AINB") (class "Default")
      (node (ref "C51") (pin "1") (pinfunction "1_1") (pintype "passive"))
      (node (ref "IC6") (pin "18") (pinfunction "AINB_18") (pintype "bidirectional"))
      (node (ref "R46") (pin "2") (pinfunction "2_2") (pintype "passive"))
    )
    (net (code "9") (name "/AOUTA+") (class "Default")
      (node (ref "C50") (pin "1") (pinfunction "1_1") (pintype "passive"))
      (node (ref "IC6") (pin "25") (pinfunction "AOUTA+_25") (pintype "bidirectional"))
      (node (ref "R58") (pin "2") (pinfunction "2_2") (pintype "passive"))
    )
    (net (code "10") (name "/AOUTA-") (class "Default")
      (node (ref "C50") (pin "2") (pinfunction "2_2") (pintype "passive"))
      (node (ref "IC6") (pin "24") (pinfunction "AOUTA-_24") (pintype "bidirectional"))
      (node (ref "R55") (pin "2") (pinfunction "2_2") (pintype "passive"))
    )
    (net (code "11") (name "/AOUTB+") (class "Default")
      (node (ref "C39") (pin "2") (pinfunction "2_2") (pintype "passive"))
      (node (ref "IC6") (pin "26") (pinfunction "AOUTB+_26") (pintype "bidirectional"))
      (node (ref "R27") (pin "2") (pinfunction "2_2") (pintype "passive"))
    )
    (net (code "12") (name "/AOUTB-") (class "Default")
      (node (ref "C39") (pin "1") (pinfunction "1_1") (pintype "passive"))
      (node (ref "IC6") (pin "27") (pinfunction "AOUTB-_27") (pintype "bidirectional"))
      (node (ref "R26") (pin "2") (pinfunction "2_2") (pintype "passive"))
    )
    (net (code "13") (name "/BOOT") (class "Default")
      (node (ref "BOOT") (pin "1") (pinfunction "1_1") (pintype "passive"))
      (node (ref "IC4") (pin "138") (pinfunction "BOOT0_138") (pintype "bidirectional"))
      (node (ref "R5") (pin "2") (pinfunction "2_2") (pintype "passive"))
    )
    (net (code "14") (name "/CS_LRCK") (class "Default")
      (node (ref "IC4") (pin "3") (pinfunction "PE4_3") (pintype "bidirectional"))
      (node (ref "IC6") (pin "4") (pinfunction "LRCK_4") (pintype "bidirectional"))
    )
    (net (code "15") (name "/CS_SCK") (class "Default")
      (node (ref "IC4") (pin "1") (pinfunction "PE2_1") (pintype "bidirectional"))
      (node (ref "IC6") (pin "11") (pinfunction "SCL/CCLK_11") (pintype "bidirectional"))
    )
    (net (code "16") (name "/CS_SCLK") (class "Default")
      (node (ref "IC4") (pin "4") (pinfunction "PE5_4") (pintype "bidirectional"))
      (node (ref "IC6") (pin "5") (pinfunction "SCLK_5") (pintype "bidirectional"))
    )
    (net (code "17") (name "/CS_SDA") (class "Default")
      (node (ref "IC4") (pin "5") (pinfunction "PE6_5") (pintype "bidirectional"))
      (node (ref "IC6") (pin "12") (pinfunction "SDA/CDIN_12") (pintype "bidirectional"))
    )
    (net (code "18") (name "/CS_SDIN") (class "Default")
      (node (ref "IC4") (pin "122") (pinfunction "PD6_122") (pintype "bidirectional"))
      (node (ref "IC6") (pin "7") (pinfunction "SDIN_7") (pintype "bidirectional"))
    )
    (net (code "19") (name "/CS_SDOUT") (class "Default")
      (node (ref "IC4") (pin "2") (pinfunction "PE3_2") (pintype "bidirectional"))
      (node (ref "IC6") (pin "6") (pinfunction "SDOUT_6") (pintype "bidirectional"))
    )
    (net (code "20") (name "/CS_VQ1") (class "Default")
      (node (ref "C34") (pin "2") (pinfunction "2_2") (pintype "passive"))
      (node (ref "C35") (pin "1") (pinfunction "1_1") (pintype "passive"))
      (node (ref "C44") (pin "1") (pinfunction "1_1") (pintype "passive"))
      (node (ref "C45") (pin "+") (pinfunction "+_+") (pintype "passive"))
      (node (ref "IC6") (pin "15") (pinfunction "VQ1_15") (pintype "bidirectional"))
      (node (ref "IC7") (pin "1") (pinfunction "+IN_1") (pintype "input"))
    )
    (net (code "21") (name "/CS_VREF") (class "Default")
      (node (ref "C51") (pin "2") (pinfunction "2_2") (pintype "passive"))
      (node (ref "C56") (pin "2") (pinfunction "2_2") (pintype "passive"))
      (node (ref "IC6") (pin "16") (pinfunction "VQ2_16") (pintype "bidirectional"))
      (node (ref "IC6") (pin "19") (pinfunction "VQ3_19") (pintype "bidirectional"))
      (node (ref "IC7") (pin "3") (pinfunction "-IN_3") (pintype "input"))
      (node (ref "IC7") (pin "4") (pinfunction "OUT_4") (pintype "output"))
      (node (ref "R29") (pin "1") (pinfunction "1_1") (pintype "passive"))
      (node (ref "R43") (pin "1") (pinfunction "1_1") (pintype "passive"))
    )
    (net (code "22") (name "/CS_~{CS}") (class "Default")
      (node (ref "IC4") (pin "124") (pinfunction "PG9_124") (pintype "bidirectional"))
      (node (ref "IC6") (pin "13") (pinfunction "AD0/~{CS}_13") (pintype "bidirectional"))
    )
    (net (code "23") (name "/CS_~{RST}") (class "Default")
      (node (ref "IC4") (pin "125") (pinfunction "PG10_125") (pintype "bidirectional"))
      (node (ref "IC6") (pin "14") (pinfunction "~{RST}_14") (pintype "bidirectional"))
      (node (ref "R3") (pin "2") (pinfunction "2_2") (pintype "passive"))
    )
    (net (code "24") (name "/CVINA") (class "Default")
      (node (ref "IC9") (pin "12") (pinfunction "+IN_12") (pintype "input"))
      (node (ref "JP3") (pin "5") (pinfunction "5_5") (pintype "passive"))
      (node (ref "R34") (pin "2") (pinfunction "2_2") (pintype "passive"))
    )
    (net (code "25") (name "/CVINB") (class "Default")
      (node (ref "IC9") (pin "10") (pinfunction "+IN_10") (pintype "input"))
      (node (ref "JP3") (pin "3") (pinfunction "3_3") (pintype "passive"))
      (node (ref "R35") (pin "2") (pinfunction "2_2") (pintype "passive"))
    )
    (net (code "26") (name "/CVOUTA") (class "Default")
      (node (ref "JP4") (pin "5") (pinfunction "5_5") (pintype "passive"))
      (node (ref "R36") (pin "2") (pinfunction "2_2") (pintype "passive"))
    )
    (net (code "27") (name "/CVOUTB") (class "Default")
      (node (ref "JP4") (pin "3") (pinfunction "3_3") (pintype "passive"))
      (node (ref "R49") (pin "2") (pinfunction "2_2") (pintype "passive"))
    )
    (net (code "28") (name "/DAC1") (class "Default")
      (node (ref "IC4") (pin "40") (pinfunction "PA4_40") (pintype "bidirectional"))
      (node (ref "R51") (pin "1") (pinfunction "1_1") (pintype "passive"))
    )
    (net (code "29") (name "/DAC2") (class "Default")
      (node (ref "IC4") (pin "41") (pinfunction "PA5_41") (pintype "bidirectional"))
      (node (ref "R50") (pin "1") (pinfunction "1_1") (pintype "passive"))
    )
    (net (code "30") (name "/DRAM_A0") (class "Default")
      (node (ref "IC4") (pin "10") (pinfunction "PF0_10") (pintype "bidirectional"))
      (node (ref "IC5") (pin "23") (pinfunction "A0_23") (pintype "bidirectional"))
    )
    (net (code "31") (name "/DRAM_A1") (class "Default")
      (node (ref "IC4") (pin "11") (pinfunction "PF1_11") (pintype "bidirectional"))
      (node (ref "IC5") (pin "24") (pinfunction "A1_24") (pintype "bidirectional"))
    )
    (net (code "32") (name "/DRAM_A2") (class "Default")
      (node (ref "IC4") (pin "12") (pinfunction "PF2_12") (pintype "bidirectional"))
      (node (ref "IC5") (pin "25") (pinfunction "A2_25") (pintype "bidirectional"))
    )
    (net (code "33") (name "/DRAM_A3") (class "Default")
      (node (ref "IC4") (pin "13") (pinfunction "PF3_13") (pintype "bidirectional"))
      (node (ref "IC5") (pin "26") (pinfunction "A3_26") (pintype "bidirectional"))
    )
    (net (code "34") (name "/DRAM_A4") (class "Default")
      (node (ref "IC4") (pin "14") (pinfunction "PF4_14") (pintype "bidirectional"))
      (node (ref "IC5") (pin "29") (pinfunction "A4_29") (pintype "bidirectional"))
    )
    (net (code "35") (name "/DRAM_A5") (class "Default")
      (node (ref "IC4") (pin "15") (pinfunction "PF5_15") (pintype "bidirectional"))
      (node (ref "IC5") (pin "30") (pinfunction "A5_30") (pintype "bidirectional"))
    )
    (net (code "36") (name "/DRAM_A6") (class "Default")
      (node (ref "IC4") (pin "50") (pinfunction "PF12_50") (pintype "bidirectional"))
      (node (ref "IC5") (pin "31") (pinfunction "A6_31") (pintype "bidirectional"))
    )
    (net (code "37") (name "/DRAM_A7") (class "Default")
      (node (ref "IC4") (pin "53") (pinfunction "PF13_53") (pintype "bidirectional"))
      (node (ref "IC5") (pin "32") (pinfunction "A7_32") (pintype "bidirectional"))
    )
    (net (code "38") (name "/DRAM_A8") (class "Default")
      (node (ref "IC4") (pin "54") (pinfunction "PF14_54") (pintype "bidirectional"))
      (node (ref "IC5") (pin "33") (pinfunction "A8_33") (pintype "bidirectional"))
    )
    (net (code "39") (name "/DRAM_A9") (class "Default")
      (node (ref "IC4") (pin "55") (pinfunction "PF15_55") (pintype "bidirectional"))
      (node (ref "IC5") (pin "34") (pinfunction "A9_34") (pintype "bidirectional"))
    )
    (net (code "40") (name "/DRAM_A10") (class "Default")
      (node (ref "IC4") (pin "56") (pinfunction "PG0_56") (pintype "bidirectional"))
      (node (ref "IC5") (pin "22") (pinfunction "A10_22") (pintype "bidirectional"))
    )
    (net (code "41") (name "/DRAM_A11") (class "Default")
      (node (ref "IC4") (pin "57") (pinfunction "PG1_57") (pintype "bidirectional"))
      (node (ref "IC5") (pin "35") (pinfunction "A11_35") (pintype "bidirectional"))
    )
    (net (code "42") (name "/DRAM_BA0") (class "Default")
      (node (ref "IC4") (pin "89") (pinfunction "PG4_89") (pintype "bidirectional"))
      (node (ref "IC5") (pin "20") (pinfunction "BA0_20") (pintype "bidirectional"))
    )
    (net (code "43") (name "/DRAM_BA1") (class "Default")
      (node (ref "IC4") (pin "90") (pinfunction "PG5_90") (pintype "bidirectional"))
      (node (ref "IC5") (pin "21") (pinfunction "BA1_21") (pintype "bidirectional"))
    )
    (net (code "44") (name "/DRAM_CKE") (class "Default")
      (node (ref "IC4") (pin "135") (pinfunction "PB5_135") (pintype "bidirectional"))
      (node (ref "IC5") (pin "37") (pinfunction "CKE_37") (pintype "bidirectional"))
    )
    (net (code "45") (name "/DRAM_CLK") (class "Default")
      (node (ref "IC4") (pin "93") (pinfunction "PG8_93") (pintype "bidirectional"))
      (node (ref "IC5") (pin "38") (pinfunction "CLK_38") (pintype "bidirectional"))
    )
    (net (code "46") (name "/DRAM_DQ0") (class "Default")
      (node (ref "IC4") (pin "85") (pinfunction "PD14_85") (pintype "bidirectional"))
      (node (ref "IC5") (pin "2") (pinfunction "DQ0_2") (pintype "bidirectional"))
    )
    (net (code "47") (name "/DRAM_DQ1") (class "Default")
      (node (ref "IC4") (pin "86") (pinfunction "PD15_86") (pintype "bidirectional"))
      (node (ref "IC5") (pin "4") (pinfunction "DQ1_4") (pintype "bidirectional"))
    )
    (net (code "48") (name "/DRAM_DQ2") (class "Default")
      (node (ref "IC4") (pin "114") (pinfunction "PD0_114") (pintype "bidirectional"))
      (node (ref "IC5") (pin "5") (pinfunction "DQ2_5") (pintype "bidirectional"))
    )
    (net (code "49") (name "/DRAM_DQ3") (class "Default")
      (node (ref "IC4") (pin "115") (pinfunction "PD1_115") (pintype "bidirectional"))
      (node (ref "IC5") (pin "7") (pinfunction "DQ3_7") (pintype "bidirectional"))
    )
    (net (code "50") (name "/DRAM_DQ4") (class "Default")
      (node (ref "IC4") (pin "58") (pinfunction "PE7_58") (pintype "bidirectional"))
      (node (ref "IC5") (pin "8") (pinfunction "DQ4_8") (pintype "bidirectional"))
    )
    (net (code "51") (name "/DRAM_DQ5") (class "Default")
      (node (ref "IC4") (pin "59") (pinfunction "PE8_59") (pintype "bidirectional"))
      (node (ref "IC5") (pin "10") (pinfunction "DQ5_10") (pintype "bidirectional"))
    )
    (net (code "52") (name "/DRAM_DQ6") (class "Default")
      (node (ref "IC4") (pin "60") (pinfunction "PE9_60") (pintype "bidirectional"))
      (node (ref "IC5") (pin "11") (pinfunction "DQ6_11") (pintype "bidirectional"))
    )
    (net (code "53") (name "/DRAM_DQ7") (class "Default")
      (node (ref "IC4") (pin "63") (pinfunction "PE10_63") (pintype "bidirectional"))
      (node (ref "IC5") (pin "13") (pinfunction "DQ7_13") (pintype "bidirectional"))
    )
    (net (code "54") (name "/DRAM_DQ8") (class "Default")
      (node (ref "IC4") (pin "64") (pinfunction "PE11_64") (pintype "bidirectional"))
      (node (ref "IC5") (pin "42") (pinfunction "DQ8_42") (pintype "bidirectional"))
    )
    (net (code "55") (name "/DRAM_DQ9") (class "Default")
      (node (ref "IC4") (pin "65") (pinfunction "PE12_65") (pintype "bidirectional"))
      (node (ref "IC5") (pin "44") (pinfunction "DQ9_44") (pintype "bidirectional"))
    )
    (net (code "56") (name "/DRAM_DQ10") (class "Default")
      (node (ref "IC4") (pin "66") (pinfunction "PE13_66") (pintype "bidirectional"))
      (node (ref "IC5") (pin "45") (pinfunction "DQ10_45") (pintype "bidirectional"))
    )
    (net (code "57") (name "/DRAM_DQ11") (class "Default")
      (node (ref "IC4") (pin "67") (pinfunction "PE14_67") (pintype "bidirectional"))
      (node (ref "IC5") (pin "47") (pinfunction "DQ11_47") (pintype "bidirectional"))
    )
    (net (code "58") (name "/DRAM_DQ12") (class "Default")
      (node (ref "IC4") (pin "68") (pinfunction "PE15_68") (pintype "bidirectional"))
      (node (ref "IC5") (pin "48") (pinfunction "DQ12_48") (pintype "bidirectional"))
    )
    (net (code "59") (name "/DRAM_DQ13") (class "Default")
      (node (ref "IC4") (pin "77") (pinfunction "PD8_77") (pintype "bidirectional"))
      (node (ref "IC5") (pin "50") (pinfunction "DQ13_50") (pintype "bidirectional"))
    )
    (net (code "60") (name "/DRAM_DQ14") (class "Default")
      (node (ref "IC4") (pin "78") (pinfunction "PD9_78") (pintype "bidirectional"))
      (node (ref "IC5") (pin "51") (pinfunction "DQ14_51") (pintype "bidirectional"))
    )
    (net (code "61") (name "/DRAM_DQ15") (class "Default")
      (node (ref "IC4") (pin "79") (pinfunction "PD10_79") (pintype "bidirectional"))
      (node (ref "IC5") (pin "53") (pinfunction "DQ15_53") (pintype "bidirectional"))
    )
    (net (code "62") (name "/DRAM_LDQM") (class "Default")
      (node (ref "IC4") (pin "141") (pinfunction "PE0_141") (pintype "bidirectional"))
      (node (ref "IC5") (pin "15") (pinfunction "LDQM_15") (pintype "bidirectional"))
    )
    (net (code "63") (name "/DRAM_UDQM") (class "Default")
      (node (ref "IC4") (pin "142") (pinfunction "PE1_142") (pintype "bidirectional"))
      (node (ref "IC5") (pin "39") (pinfunction "UDQM_39") (pintype "bidirectional"))
    )
    (net (code "64") (name "/DRAM_~{CAS}") (class "Default")
      (node (ref "IC4") (pin "132") (pinfunction "PG15_132") (pintype "bidirectional"))
      (node (ref "IC5") (pin "17") (pinfunction "~{CAS}_17") (pintype "bidirectional"))
    )
    (net (code "65") (name "/DRAM_~{CS}") (class "Default")
      (node (ref "IC4") (pin "136") (pinfunction "PB6_136") (pintype "bidirectional"))
      (node (ref "IC5") (pin "19") (pinfunction "~{CS}_19") (pintype "bidirectional"))
    )
    (net (code "66") (name "/DRAM_~{RAS}") (class "Default")
      (node (ref "IC4") (pin "49") (pinfunction "PF11_49") (pintype "bidirectional"))
      (node (ref "IC5") (pin "18") (pinfunction "~{RAS}_18") (pintype "bidirectional"))
    )
    (net (code "67") (name "/DRAM_~{WE}") (class "Default")
      (node (ref "IC4") (pin "26") (pinfunction "PC0_26") (pintype "bidirectional"))
      (node (ref "IC5") (pin "16") (pinfunction "~{WE}_16") (pintype "bidirectional"))
    )
    (net (code "68") (name "/ENC1_A") (class "Default")
      (node (ref "IC4") (pin "42") (pinfunction "PA6_42") (pintype "bidirectional"))
      (node (ref "JP2") (pin "2") (pinfunction "2_2") (pintype "passive"))
    )
    (net (code "69") (name "/ENC1_B") (class "Default")
      (node (ref "IC4") (pin "43") (pinfunction "PA7_43") (pintype "bidirectional"))
      (node (ref "JP2") (pin "3") (pinfunction "3_3") (pintype "passive"))
    )
    (net (code "70") (name "/ENC1_SW") (class "Default")
      (node (ref "IC4") (pin "129") (pinfunction "PG14_129") (pintype "bidirectional"))
      (node (ref "JP2") (pin "1") (pinfunction "1_1") (pintype "passive"))
    )
    (net (code "71") (name "/ENC2_A") (class "Default")
      (node (ref "IC4") (pin "110") (pinfunction "PA15_110") (pintype "bidirectional"))
      (node (ref "JP2") (pin "5") (pinfunction "5_5") (pintype "passive"))
    )
    (net (code "72") (name "/ENC2_B") (class "Default")
      (node (ref "IC4") (pin "133") (pinfunction "PB3_133") (pintype "bidirectional"))
      (node (ref "JP2") (pin "6") (pinfunction "6_6") (pintype "passive"))
    )
    (net (code "73") (name "/ENC2_SW") (class "Default")
      (node (ref "IC4") (pin "134") (pinfunction "PB4_134") (pintype "bidirectional"))
      (node (ref "JP2") (pin "4") (pinfunction "4_4") (pintype "passive"))
    )
    (net (code "74") (name "/FLASH_CLK") (class "Default")
      (node (ref "IC2") (pin "6") (pinfunction "C_6") (pintype "bidirectional"))
      (node (ref "IC4") (pin "19") (pinfunction "PF7_19") (pintype "bidirectional"))
    )
    (net (code "75") (name "/FLASH_HOLD") (class "Default")
      (node (ref "IC2") (pin "7") (pinfunction "HOLD#/DQ3_7") (pintype "bidirectional"))
      (node (ref "IC4") (pin "22") (pinfunction "PF10_22") (pintype "bidirectional"))
    )
    (net (code "76") (name "/FLASH_MISO") (class "Default")
      (node (ref "IC2") (pin "2") (pinfunction "DQ1_2") (pintype "bidirectional"))
      (node (ref "IC4") (pin "20") (pinfunction "PF8_20") (pintype "bidirectional"))
    )
    (net (code "77") (name "/FLASH_MOSI") (class "Default")
      (node (ref "IC2") (pin "5") (pinfunction "DQ0_5") (pintype "bidirectional"))
      (node (ref "IC4") (pin "21") (pinfunction "PF9_21") (pintype "bidirectional"))
    )
    (net (code "78") (name "/FLASH_NCS") (class "Default")
      (node (ref "IC2") (pin "1") (pinfunction "S#_1") (pintype "bidirectional"))
      (node (ref "IC4") (pin "18") (pinfunction "PF6_18") (pintype "bidirectional"))
      (node (ref "R2") (pin "2") (pinfunction "2_2") (pintype "passive"))
    )
    (net (code "79") (name "/FLASH_W") (class "Default")
      (node (ref "IC2") (pin "3") (pinfunction "VPP/W#/DQ2_3") (pintype "bidirectional"))
      (node (ref "IC4") (pin "7") (pinfunction "PC13_7") (pintype "bidirectional"))
    )
    (net (code "80") (name "/I2C_SCL") (class "Default")
      (node (ref "I2C") (pin "2") (pinfunction "2_2") (pintype "passive"))
      (node (ref "IC4") (pin "139") (pinfunction "PB8_139") (pintype "bidirectional"))
    )
    (net (code "81") (name "/I2C_SDA") (class "Default")
      (node (ref "I2C") (pin "3") (pinfunction "3_3") (pintype "passive"))
      (node (ref "IC4") (pin "137") (pinfunction "PB7_137") (pintype "bidirectional"))
    )
    (net (code "82") (name "/INL") (class "Default")
      (node (ref "JP3") (pin "2") (pinfunction "2_2") (pintype "passive"))
      (node (ref "R30") (pin "1") (pinfunction "1_1") (pintype "passive"))
    )
    (net (code "83") (name "/INR") (class "Default")
      (node (ref "JP3") (pin "1") (pinfunction "1_1") (pintype "passive"))
      (node (ref "R44") (pin "1") (pinfunction "1_1") (pintype "passive"))
    )
    (net (code "84") (name "/NRST") (class "Default")
      (node (ref "IC4") (pin "25") (pinfunction "NRST_25") (pintype "bidirectional"))
      (node (ref "X2") (pin "5") (pinfunction "S_5") (pintype "passive"))
    )
    (net (code "85") (name "/OLED_CS") (class "Default")
      (node (ref "IC4") (pin "70") (pinfunction "PB11_70") (pintype "bidirectional"))
      (node (ref "X1") (pin "8") (pinfunction "1_8") (pintype "passive"))
    )
    (net (code "86") (name "/OLED_DC") (class "Default")
      (node (ref "IC4") (pin "29") (pinfunction "PC3_29") (pintype "bidirectional"))
      (node (ref "X1") (pin "10") (pinfunction "1_10") (pintype "passive"))
    )
    (net (code "87") (name "/OLED_MOSI") (class "Default")
      (node (ref "IC4") (pin "27") (pinfunction "PC1_27") (pintype "bidirectional"))
      (node (ref "X1") (pin "14") (pinfunction "1_14") (pintype "passive"))
    )
    (net (code "88") (name "/OLED_RST") (class "Default")
      (node (ref "IC4") (pin "28") (pinfunction "PC2_28") (pintype "bidirectional"))
      (node (ref "X1") (pin "9") (pinfunction "1_9") (pintype "passive"))
    )
    (net (code "89") (name "/OLED_SCK") (class "Default")
      (node (ref "IC4") (pin "69") (pinfunction "PB10_69") (pintype "bidirectional"))
      (node (ref "X1") (pin "13") (pinfunction "1_13") (pintype "passive"))
    )
    (net (code "90") (name "/OUTL") (class "Default")
      (node (ref "JP4") (pin "2") (pinfunction "2_2") (pintype "passive"))
      (node (ref "R38") (pin "1") (pinfunction "1_1") (pintype "passive"))
    )
    (net (code "91") (name "/OUTR") (class "Default")
      (node (ref "JP4") (pin "1") (pinfunction "1_1") (pintype "passive"))
      (node (ref "R24") (pin "1") (pinfunction "1_1") (pintype "passive"))
    )
    (net (code "92") (name "/SWCLK") (class "Default")
      (node (ref "IC4") (pin "109") (pinfunction "PA14_109") (pintype "bidirectional"))
      (node (ref "X2") (pin "2") (pinfunction "S_2") (pintype "passive"))
    )
    (net (code "93") (name "/SWDIO") (class "Default")
      (node (ref "IC4") (pin "105") (pinfunction "PA13_105") (pintype "bidirectional"))
      (node (ref "X2") (pin "4") (pinfunction "S_4") (pintype "passive"))
    )
    (net (code "94") (name "/SW_A") (class "Default")
      (node (ref "IC4") (pin "111") (pinfunction "PC10_111") (pintype "bidirectional"))
      (node (ref "JP3") (pin "8") (pinfunction "8_8") (pintype "passive"))
    )
    (net (code "95") (name "/SW_B") (class "Default")
      (node (ref "IC4") (pin "113") (pinfunction "PC12_113") (pintype "bidirectional"))
      (node (ref "JP4") (pin "8") (pinfunction "8_8") (pintype "passive"))
    )
    (net (code "96") (name "/TRINA") (class "Default")
      (node (ref "JP3") (pin "7") (pinfunction "7_7") (pintype "passive"))
      (node (ref "R8") (pin "1") (pinfunction "1_1") (pintype "passive"))
    )
    (net (code "97") (name "/TRINB") (class "Default")
      (node (ref "JP3") (pin "6") (pinfunction "6_6") (pintype "passive"))
      (node (ref "R13") (pin "1") (pinfunction "1_1") (pintype "passive"))
    )
    (net (code "98") (name "/TROUTA") (class "Default")
      (node (ref "JP4") (pin "7") (pinfunction "7_7") (pintype "passive"))
      (node (ref "R18") (pin "2") (pinfunction "2_2") (pintype "passive"))
      (node (ref "R20") (pin "2") (pinfunction "2_2") (pintype "passive"))
    )
    (net (code "99") (name "/TROUTB") (class "Default")
      (node (ref "JP4") (pin "6") (pinfunction "6_6") (pintype "passive"))
      (node (ref "R22") (pin "2") (pinfunction "2_2") (pintype "passive"))
      (node (ref "R23") (pin "2") (pinfunction "2_2") (pintype "passive"))
    )
    (net (code "100") (name "/TR_IN_A") (class "Default")
      (node (ref "IC4") (pin "112") (pinfunction "PC11_112") (pintype "bidirectional"))
      (node (ref "Q3") (pin "3") (pinfunction "C_3") (pintype "passive"))
      (node (ref "R6") (pin "2") (pinfunction "2_2") (pintype "passive"))
    )
    (net (code "101") (name "/TR_IN_B") (class "Default")
      (node (ref "IC4") (pin "116") (pinfunction "PD2_116") (pintype "bidirectional"))
      (node (ref "Q6") (pin "3") (pinfunction "C_3") (pintype "passive"))
      (node (ref "R11") (pin "2") (pinfunction "2_2") (pintype "passive"))
    )
    (net (code "102") (name "/TR_OUT_A") (class "Default")
      (node (ref "IC4") (pin "118") (pinfunction "PD4_118") (pintype "bidirectional"))
      (node (ref "R9") (pin "2") (pinfunction "2_2") (pintype "passive"))
    )
    (net (code "103") (name "/TR_OUT_B") (class "Default")
      (node (ref "IC4") (pin "117") (pinfunction "PD3_117") (pintype "bidirectional"))
      (node (ref "R10") (pin "2") (pinfunction "2_2") (pintype "passive"))
    )
    (net (code "104") (name "/UART5_RX") (class "Default")
      (node (ref "IC4") (pin "73") (pinfunction "PB12_73") (pintype "bidirectional"))
      (node (ref "JP1") (pin "4") (pinfunction "4_4") (pintype "passive"))
    )
    (net (code "105") (name "/UART5_TX") (class "Default")
      (node (ref "IC4") (pin "74") (pinfunction "PB13_74") (pintype "bidirectional"))
      (node (ref "JP1") (pin "5") (pinfunction "5_5") (pintype "passive"))
    )
    (net (code "106") (name "/UART_MCU_RX") (class "Default")
      (node (ref "BUS") (pin "1") (pinfunction "1_1") (pintype "passive"))
      (node (ref "IC4") (pin "37") (pinfunction "PA3_37") (pintype "bidirectional"))
    )
    (net (code "107") (name "/UART_MCU_TX") (class "Default")
      (node (ref "BUS") (pin "3") (pinfunction "3_3") (pintype "passive"))
      (node (ref "IC4") (pin "36") (pinfunction "PA2_36") (pintype "bidirectional"))
    )
    (net (code "108") (name "/USBD_DM") (class "Default")
      (node (ref "IC3") (pin "1") (pinfunction "I/O_1_1") (pintype "bidirectional"))
      (node (ref "IC4") (pin "103") (pinfunction "PA11_103") (pintype "bidirectional"))
    )
    (net (code "109") (name "/USBD_DP") (class "Default")
      (node (ref "IC3") (pin "3") (pinfunction "I/O_2_3") (pintype "bidirectional"))
      (node (ref "IC4") (pin "104") (pinfunction "PA12_104") (pintype "bidirectional"))
    )
    (net (code "110") (name "/USBD_VBUS") (class "Default")
      (node (ref "IC3") (pin "5") (pinfunction "VBUS_5") (pintype "bidirectional"))
      (node (ref "IC4") (pin "101") (pinfunction "PA9_101") (pintype "bidirectional"))
      (node (ref "JP1") (pin "1") (pinfunction "1_1") (pintype "passive"))
    )
    (net (code "111") (name "/USBH_DM") (class "Default")
      (node (ref "IC4") (pin "75") (pinfunction "PB14_75") (pintype "bidirectional"))
      (node (ref "JP1") (pin "7") (pinfunction "7_7") (pintype "passive"))
    )
    (net (code "112") (name "/USBH_DP") (class "Default")
      (node (ref "IC4") (pin "76") (pinfunction "PB15_76") (pintype "bidirectional"))
      (node (ref "JP1") (pin "8") (pinfunction "8_8") (pintype "passive"))
    )
    (net (code "113") (name "/USBH_PWR_EN") (class "Default")
      (node (ref "IC1") (pin "3") (pinfunction "EN_3") (pintype "input"))
      (node (ref "IC4") (pin "99") (pinfunction "PC9_99") (pintype "bidirectional"))
    )
    (net (code "114") (name "/USBH_PWR_FAULT") (class "Default")
      (node (ref "IC1") (pin "4") (pinfunction "FAULT_4") (pintype "output"))
      (node (ref "IC4") (pin "102") (pinfunction "PA10_102") (pintype "bidirectional"))
    )
    (net (code "115") (name "/USBH_VBUS") (class "Default")
      (node (ref "IC1") (pin "6") (pinfunction "VOUT_6") (pintype "output"))
      (node (ref "JP1") (pin "6") (pinfunction "6_6") (pintype "passive"))
    )
    (net (code "116") (name "/VDDA") (class "Default")
      (node (ref "C17") (pin "1") (pinfunction "1_1") (pintype "passive"))
      (node (ref "C5") (pin "1") (pinfunction "1_1") (pintype "passive"))
      (node (ref "IC4") (pin "33") (pinfunction "VDDA_33") (pintype "bidirectional"))
      (node (ref "L1") (pin "1") (pinfunction "1_1") (pintype "passive"))
    )
    (net (code "117") (name "GND") (class "Default")
      (node (ref "BUS") (pin "2") (pinfunction "2_2") (pintype "passive"))
      (node (ref "C1") (pin "-") (pinfunction "-_-") (pintype "passive"))
      (node (ref "C10") (pin "-") (pinfunction "-_-") (pintype "passive"))
      (node (ref "C11") (pin "2") (pinfunction "2_2") (pintype "passive"))
      (node (ref "C12") (pin "2") (pinfunction "2_2") (pintype "passive"))
      (node (ref "C13") (pin "2") (pinfunction "2_2") (pintype "passive"))
      (node (ref "C14") (pin "2") (pinfunction "2_2") (pintype "passive"))
      (node (ref "C15") (pin "2") (pinfunction "2_2") (pintype "passive"))
      (node (ref "C16") (pin "2") (pinfunction "2_2") (pintype "passive"))
      (node (ref "C17") (pin "2") (pinfunction "2_2") (pintype "passive"))
      (node (ref "C18") (pin "2") (pinfunction "2_2") (pintype "passive"))
      (node (ref "C19") (pin "2") (pinfunction "2_2") (pintype "passive"))
      (node (ref "C2") (pin "C") (pinfunction "-_C") (pintype "passive"))
      (node (ref "C20") (pin "2") (pinfunction "2_2") (pintype "passive"))
      (node (ref "C21") (pin "2") (pinfunction "2_2") (pintype "passive"))
      (node (ref "C22") (pin "2") (pinfunction "2_2") (pintype "passive"))
      (node (ref "C23") (pin "2") (pinfunction "2_2") (pintype "passive"))
      (node (ref "C24") (pin "2") (pinfunction "2_2") (pintype "passive"))
      (node (ref "C25") (pin "2") (pinfunction "2_2") (pintype "passive"))
      (node (ref "C26") (pin "2") (pinfunction "2_2") (pintype "passive"))
      (node (ref "C27") (pin "2") (pinfunction "2_2") (pintype "passive"))
      (node (ref "C28") (pin "2") (pinfunction "2_2") (pintype "passive"))
      (node (ref "C29") (pin "2") (pinfunction "2_2") (pintype "passive"))
      (node (ref "C3") (pin "1") (pinfunction "1_1") (pintype "passive"))
      (node (ref "C30") (pin "2") (pinfunction "2_2") (pintype "passive"))
      (node (ref "C31") (pin "2") (pinfunction "2_2") (pintype "passive"))
      (node (ref "C32") (pin "2") (pinfunction "2_2") (pintype "passive"))
      (node (ref "C33") (pin "2") (pinfunction "2_2") (pintype "passive"))
      (node (ref "C34") (pin "1") (pinfunction "1_1") (pintype "passive"))
      (node (ref "C35") (pin "2") (pinfunction "2_2") (pintype "passive"))
      (node (ref "C36") (pin "2") (pinfunction "2_2") (pintype "passive"))
      (node (ref "C37") (pin "-") (pinfunction "-_-") (pintype "passive"))
      (node (ref "C38") (pin "2") (pinfunction "2_2") (pintype "passive"))
      (node (ref "C4") (pin "1") (pinfunction "1_1") (pintype "passive"))
      (node (ref "C40") (pin "2") (pinfunction "2_2") (pintype "passive"))
      (node (ref "C41") (pin "2") (pinfunction "2_2") (pintype "passive"))
      (node (ref "C42") (pin "2") (pinfunction "2_2") (pintype "passive"))
      (node (ref "C43") (pin "2") (pinfunction "2_2") (pintype "passive"))
      (node (ref "C44") (pin "2") (pinfunction "2_2") (pintype "passive"))
      (node (ref "C45") (pin "-") (pinfunction "-_-") (pintype "passive"))
      (node (ref "C46") (pin "2") (pinfunction "2_2") (pintype "passive"))
      (node (ref "C47") (pin "2") (pinfunction "2_2") (pintype "passive"))
      (node (ref "C48") (pin "2") (pinfunction "2_2") (pintype "passive"))
      (node (ref "C49") (pin "2") (pinfunction "2_2") (pintype "passive"))
      (node (ref "C5") (pin "2") (pinfunction "2_2") (pintype "passive"))
      (node (ref "C52") (pin "2") (pinfunction "2_2") (pintype "passive"))
      (node (ref "C53") (pin "2") (pinfunction "2_2") (pintype "passive"))
      (node (ref "C55") (pin "2") (pinfunction "2_2") (pintype "passive"))
      (node (ref "C58") (pin "2") (pinfunction "2_2") (pintype "passive"))
      (node (ref "C59") (pin "2") (pinfunction "2_2") (pintype "passive"))
      (node (ref "C6") (pin "1") (pinfunction "1_1") (pintype "passive"))
      (node (ref "C60") (pin "2") (pinfunction "2_2") (pintype "passive"))
      (node (ref "C62") (pin "2") (pinfunction "2_2") (pintype "passive"))
      (node (ref "C63") (pin "2") (pinfunction "2_2") (pintype "passive"))
      (node (ref "C64") (pin "2") (pinfunction "2_2") (pintype "passive"))
      (node (ref "C66") (pin "2") (pinfunction "2_2") (pintype "passive"))
      (node (ref "C67") (pin "2") (pinfunction "2_2") (pintype "passive"))
      (node (ref "C7") (pin "1") (pinfunction "1_1") (pintype "passive"))
      (node (ref "C70") (pin "2") (pinfunction "2_2") (pintype "passive"))
      (node (ref "C8") (pin "1") (pinfunction "1_1") (pintype "passive"))
      (node (ref "C9") (pin "2") (pinfunction "2_2") (pintype "passive"))
      (node (ref "D1") (pin "1") (pinfunction "A1_1") (pintype "passive"))
      (node (ref "D2") (pin "1") (pinfunction "A1_1") (pintype "passive"))
      (node (ref "I2C") (pin "1") (pinfunction "1_1") (pintype "passive"))
      (node (ref "IC1") (pin "2") (pinfunction "GND_2") (pintype "power_in"))
      (node (ref "IC2") (pin "4") (pinfunction "VSS_4") (pintype "bidirectional"))
      (node (ref "IC3") (pin "2") (pinfunction "GND_2") (pintype "bidirectional"))
      (node (ref "IC4") (pin "107") (pinfunction "VSS6_107") (pintype "bidirectional"))
      (node (ref "IC4") (pin "120") (pinfunction "VSS7_120") (pintype "bidirectional"))
      (node (ref "IC4") (pin "130") (pinfunction "VSS8_130") (pintype "bidirectional"))
      (node (ref "IC4") (pin "143") (pinfunction "PDR_ON_143") (pintype "bidirectional"))
      (node (ref "IC4") (pin "16") (pinfunction "VSS_16") (pintype "bidirectional"))
      (node (ref "IC4") (pin "31") (pinfunction "VSSA_31") (pintype "bidirectional"))
      (node (ref "IC4") (pin "38") (pinfunction "VSS1_38") (pintype "bidirectional"))
      (node (ref "IC4") (pin "51") (pinfunction "VSS2_51") (pintype "bidirectional"))
      (node (ref "IC4") (pin "61") (pinfunction "VSS3_61") (pintype "bidirectional"))
      (node (ref "IC4") (pin "83") (pinfunction "VSS4_83") (pintype "bidirectional"))
      (node (ref "IC4") (pin "94") (pinfunction "VSS5_94") (pintype "bidirectional"))
      (node (ref "IC5") (pin "12") (pinfunction "GNDQ1_12") (pintype "bidirectional"))
      (node (ref "IC5") (pin "28") (pinfunction "GND1_28") (pintype "bidirectional"))
      (node (ref "IC5") (pin "41") (pinfunction "GND_41") (pintype "bidirectional"))
      (node (ref "IC5") (pin "46") (pinfunction "GNDQ2_46") (pintype "bidirectional"))
      (node (ref "IC5") (pin "52") (pinfunction "GNDQ3_52") (pintype "bidirectional"))
      (node (ref "IC5") (pin "54") (pinfunction "GND2_54") (pintype "bidirectional"))
      (node (ref "IC5") (pin "6") (pinfunction "GNDQ_6") (pintype "bidirectional"))
      (node (ref "IC6") (pin "21") (pinfunction "AGND_21") (pintype "bidirectional"))
      (node (ref "IC6") (pin "8") (pinfunction "DGND_8") (pintype "bidirectional"))
      (node (ref "JP1") (pin "9") (pinfunction "9_9") (pintype "passive"))
      (node (ref "JP2") (pin "9") (pinfunction "9_9") (pintype "passive"))
      (node (ref "JP3") (pin "4") (pinfunction "4_4") (pintype "passive"))
      (node (ref "JP4") (pin "4") (pinfunction "4_4") (pintype "passive"))
      (node (ref "PWR") (pin "3") (pinfunction "3_3") (pintype "passive"))
      (node (ref "PWR") (pin "4") (pinfunction "4_4") (pintype "passive"))
      (node (ref "PWR") (pin "5") (pinfunction "5_5") (pintype "passive"))
      (node (ref "PWR") (pin "6") (pinfunction "6_6") (pintype "passive"))
      (node (ref "PWR") (pin "7") (pinfunction "7_7") (pintype "passive"))
      (node (ref "PWR") (pin "8") (pinfunction "8_8") (pintype "passive"))
      (node (ref "Q1") (pin "1") (pinfunction "G_1") (pintype "passive"))
      (node (ref "Q2") (pin "1") (pinfunction "G_1") (pintype "passive"))
      (node (ref "Q3") (pin "2") (pinfunction "E_2") (pintype "passive"))
      (node (ref "Q4") (pin "2") (pinfunction "E_2") (pintype "passive"))
      (node (ref "Q5") (pin "2") (pinfunction "E_2") (pintype "passive"))
      (node (ref "Q6") (pin "2") (pinfunction "E_2") (pintype "passive"))
      (node (ref "R1") (pin "1") (pinfunction "1_1") (pintype "passive"))
      (node (ref "R12") (pin "2") (pinfunction "2_2") (pintype "passive"))
      (node (ref "R15") (pin "2") (pinfunction "2_2") (pintype "passive"))
      (node (ref "R19") (pin "2") (pinfunction "2_2") (pintype "passive"))
      (node (ref "R20") (pin "1") (pinfunction "1_1") (pintype "passive"))
      (node (ref "R23") (pin "1") (pinfunction "1_1") (pintype "passive"))
      (node (ref "R28") (pin "2") (pinfunction "2_2") (pintype "passive"))
      (node (ref "R3") (pin "1") (pinfunction "1_1") (pintype "passive"))
      (node (ref "R34") (pin "1") (pinfunction "1_1") (pintype "passive"))
      (node (ref "R35") (pin "1") (pinfunction "1_1") (pintype "passive"))
      (node (ref "R41") (pin "2") (pinfunction "2_2") (pintype "passive"))
      (node (ref "R42") (pin "2") (pinfunction "2_2") (pintype "passive"))
      (node (ref "R48") (pin "1") (pinfunction "1_1") (pintype "passive"))
      (node (ref "R5") (pin "1") (pinfunction "1_1") (pintype "passive"))
      (node (ref "R53") (pin "1") (pinfunction "1_1") (pintype "passive"))
      (node (ref "R59") (pin "2") (pinfunction "2_2") (pintype "passive"))
      (node (ref "R7") (pin "2") (pinfunction "2_2") (pintype "passive"))
      (node (ref "U1") (pin "1") (pinfunction "ADJ_1") (pintype "input"))
      (node (ref "X1") (pin "1") (pinfunction "1_1") (pintype "passive"))
      (node (ref "X1") (pin "11") (pinfunction "1_11") (pintype "passive"))
      (node (ref "X1") (pin "12") (pinfunction "1_12") (pintype "passive"))
      (node (ref "X1") (pin "16") (pinfunction "1_16") (pintype "passive"))
      (node (ref "X1") (pin "17") (pinfunction "1_17") (pintype "passive"))
      (node (ref "X1") (pin "18") (pinfunction "1_18") (pintype "passive"))
      (node (ref "X1") (pin "19") (pinfunction "1_19") (pintype "passive"))
      (node (ref "X1") (pin "2") (pinfunction "1_2") (pintype "passive"))
      (node (ref "X1") (pin "20") (pinfunction "1_20") (pintype "passive"))
      (node (ref "X1") (pin "24") (pinfunction "1_24") (pintype "passive"))
      (node (ref "X1") (pin "3") (pinfunction "1_3") (pintype "passive"))
      (node (ref "X1") (pin "6") (pinfunction "1_6") (pintype "passive"))
      (node (ref "X1") (pin "7") (pinfunction "1_7") (pintype "passive"))
      (node (ref "X2") (pin "3") (pinfunction "S_3") (pintype "passive"))
    )
    (net (code "118") (name "Net-(C2-+)") (class "Default")
      (node (ref "C2") (pin "A") (pinfunction "+_A") (pintype "passive"))
      (node (ref "X1") (pin "22") (pinfunction "1_22") (pintype "passive"))
    )
    (net (code "119") (name "Net-(C54-Pad1)") (class "Default")
      (node (ref "C54") (pin "1") (pinfunction "1_1") (pintype "passive"))
      (node (ref "R27") (pin "1") (pinfunction "1_1") (pintype "passive"))
      (node (ref "R40") (pin "2") (pinfunction "2_2") (pintype "passive"))
      (node (ref "R41") (pin "1") (pinfunction "1_1") (pintype "passive"))
    )
    (net (code "120") (name "Net-(C54-Pad2)") (class "Default")
      (node (ref "C54") (pin "2") (pinfunction "2_2") (pintype "passive"))
      (node (ref "R25") (pin "2") (pinfunction "2_2") (pintype "passive"))
      (node (ref "R26") (pin "1") (pinfunction "1_1") (pintype "passive"))
      (node (ref "R39") (pin "2") (pinfunction "2_2") (pintype "passive"))
    )
    (net (code "121") (name "Net-(C69-Pad1)") (class "Default")
      (node (ref "C69") (pin "1") (pinfunction "1_1") (pintype "passive"))
      (node (ref "R57") (pin "2") (pinfunction "2_2") (pintype "passive"))
      (node (ref "R58") (pin "1") (pinfunction "1_1") (pintype "passive"))
      (node (ref "R59") (pin "1") (pinfunction "1_1") (pintype "passive"))
    )
    (net (code "122") (name "Net-(C69-Pad2)") (class "Default")
      (node (ref "C69") (pin "2") (pinfunction "2_2") (pintype "passive"))
      (node (ref "R54") (pin "2") (pinfunction "2_2") (pintype "passive"))
      (node (ref "R55") (pin "1") (pinfunction "1_1") (pintype "passive"))
      (node (ref "R56") (pin "2") (pinfunction "2_2") (pintype "passive"))
    )
    (net (code "123") (name "Net-(D1-C1A2)") (class "Default")
      (node (ref "C52") (pin "1") (pinfunction "1_1") (pintype "passive"))
      (node (ref "D1") (pin "3") (pinfunction "C1A2_3") (pintype "passive"))
      (node (ref "R14") (pin "1") (pinfunction "1_1") (pintype "passive"))
      (node (ref "R15") (pin "1") (pinfunction "1_1") (pintype "passive"))
      (node (ref "R33") (pin "2") (pinfunction "2_2") (pintype "passive"))
    )
    (net (code "124") (name "Net-(D2-C1A2)") (class "Default")
      (node (ref "C53") (pin "1") (pinfunction "1_1") (pintype "passive"))
      (node (ref "D2") (pin "3") (pinfunction "C1A2_3") (pintype "passive"))
      (node (ref "R17") (pin "1") (pinfunction "1_1") (pintype "passive"))
      (node (ref "R19") (pin "1") (pinfunction "1_1") (pintype "passive"))
      (node (ref "R37") (pin "2") (pinfunction "2_2") (pintype "passive"))
    )
    (net (code "125") (name "Net-(IC3-I{slash}O1)") (class "Default")
      (node (ref "IC3") (pin "6") (pinfunction "I/O1_6") (pintype "bidirectional"))
      (node (ref "JP1") (pin "2") (pinfunction "2_2") (pintype "passive"))
    )
    (net (code "126") (name "Net-(IC3-I{slash}O2)") (class "Default")
      (node (ref "IC3") (pin "4") (pinfunction "I/O2_4") (pintype "bidirectional"))
      (node (ref "JP1") (pin "3") (pinfunction "3_3") (pintype "passive"))
    )
    (net (code "127") (name "Net-(IC4A-PH0)") (class "Default")
      (node (ref "C15") (pin "1") (pinfunction "1_1") (pintype "passive"))
      (node (ref "IC4") (pin "23") (pinfunction "PH0_23") (pintype "bidirectional"))
      (node (ref "Y1") (pin "2") (pinfunction "2_2") (pintype "passive"))
    )
    (net (code "128") (name "Net-(IC4A-PH1)") (class "Default")
      (node (ref "C14") (pin "1") (pinfunction "1_1") (pintype "passive"))
      (node (ref "IC4") (pin "24") (pinfunction "PH1_24") (pintype "bidirectional"))
      (node (ref "Y1") (pin "1") (pinfunction "1_1") (pintype "passive"))
    )
    (net (code "129") (name "Net-(IC4B-VCAP_1)") (class "Default")
      (node (ref "C19") (pin "1") (pinfunction "1_1") (pintype "passive"))
      (node (ref "IC4") (pin "71") (pinfunction "VCAP_1_71") (pintype "bidirectional"))
    )
    (net (code "130") (name "Net-(IC4C-VCAP_2)") (class "Default")
      (node (ref "C25") (pin "1") (pinfunction "1_1") (pintype "passive"))
      (node (ref "IC4") (pin "106") (pinfunction "VCAP_2_106") (pintype "bidirectional"))
    )
    (net (code "131") (name "Net-(IC6-FILT+)") (class "Default")
      (node (ref "C36") (pin "1") (pinfunction "1_1") (pintype "passive"))
      (node (ref "C37") (pin "+") (pinfunction "+_+") (pintype "passive"))
      (node (ref "IC6") (pin "22") (pinfunction "FILT+_22") (pintype "bidirectional"))
    )
    (net (code "132") (name "Net-(IC6-VA)") (class "Default")
      (node (ref "C46") (pin "1") (pinfunction "1_1") (pintype "passive"))
      (node (ref "C47") (pin "1") (pinfunction "1_1") (pintype "passive"))
      (node (ref "IC6") (pin "20") (pinfunction "VA_20") (pintype "bidirectional"))
      (node (ref "L2") (pin "2") (pinfunction "2_2") (pintype "passive"))
    )
    (net (code "133") (name "Net-(IC6-VD)") (class "Default")
      (node (ref "C29") (pin "1") (pinfunction "1_1") (pintype "passive"))
      (node (ref "C30") (pin "1") (pinfunction "1_1") (pintype "passive"))
      (node (ref "IC6") (pin "9") (pinfunction "VD_9") (pintype "bidirectional"))
      (node (ref "R4") (pin "1") (pinfunction "1_1") (pintype "passive"))
    )
    (net (code "134") (name "Net-(IC6-XTI)") (class "Default")
      (node (ref "C41") (pin "1") (pinfunction "1_1") (pintype "passive"))
      (node (ref "IC6") (pin "2") (pinfunction "XTI_2") (pintype "bidirectional"))
      (node (ref "Y2") (pin "2") (pinfunction "2_2") (pintype "passive"))
    )
    (net (code "135") (name "Net-(IC6-XTO)") (class "Default")
      (node (ref "C40") (pin "1") (pinfunction "1_1") (pintype "passive"))
      (node (ref "IC6") (pin "1") (pinfunction "XTO_1") (pintype "bidirectional"))
      (node (ref "Y2") (pin "1") (pinfunction "1_1") (pintype "passive"))
    )
    (net (code "136") (name "Net-(IC8A-+IN)") (class "Default")
      (node (ref "IC8") (pin "3") (pinfunction "+IN_3") (pintype "input"))
      (node (ref "R28") (pin "1") (pinfunction "1_1") (pintype "passive"))
      (node (ref "R29") (pin "2") (pinfunction "2_2") (pintype "passive"))
    )
    (net (code "137") (name "Net-(IC8A--IN)") (class "Default")
      (node (ref "C57") (pin "1") (pinfunction "1_1") (pintype "passive"))
      (node (ref "IC8") (pin "2") (pinfunction "-IN_2") (pintype "input"))
      (node (ref "R30") (pin "2") (pinfunction "2_2") (pintype "passive"))
      (node (ref "R32") (pin "1") (pinfunction "1_1") (pintype "passive"))
    )
    (net (code "138") (name "Net-(IC8A-OUT)") (class "Default")
      (node (ref "C57") (pin "2") (pinfunction "2_2") (pintype "passive"))
      (node (ref "IC8") (pin "1") (pinfunction "OUT_1") (pintype "output"))
      (node (ref "R31") (pin "1") (pinfunction "1_1") (pintype "passive"))
      (node (ref "R32") (pin "2") (pinfunction "2_2") (pintype "passive"))
    )
    (net (code "139") (name "Net-(IC8B-+IN)") (class "Default")
      (node (ref "IC8") (pin "5") (pinfunction "+IN_5") (pintype "input"))
      (node (ref "R42") (pin "1") (pinfunction "1_1") (pintype "passive"))
      (node (ref "R43") (pin "2") (pinfunction "2_2") (pintype "passive"))
    )
    (net (code "140") (name "Net-(IC8B--IN)") (class "Default")
      (node (ref "C65") (pin "1") (pinfunction "1_1") (pintype "passive"))
      (node (ref "IC8") (pin "6") (pinfunction "-IN_6") (pintype "input"))
      (node (ref "R44") (pin "2") (pinfunction "2_2") (pintype "passive"))
      (node (ref "R45") (pin "1") (pinfunction "1_1") (pintype "passive"))
    )
    (net (code "141") (name "Net-(IC8B-OUT)") (class "Default")
      (node (ref "C65") (pin "2") (pinfunction "2_2") (pintype "passive"))
      (node (ref "IC8") (pin "7") (pinfunction "OUT_7") (pintype "output"))
      (node (ref "R45") (pin "2") (pinfunction "2_2") (pintype "passive"))
      (node (ref "R46") (pin "1") (pinfunction "1_1") (pintype "passive"))
    )
    (net (code "142") (name "Net-(IC9A-+IN)") (class "Default")
      (node (ref "C66") (pin "1") (pinfunction "1_1") (pintype "passive"))
      (node (ref "IC9") (pin "3") (pinfunction "+IN_3") (pintype "input"))
      (node (ref "R50") (pin "2") (pinfunction "2_2") (pintype "passive"))
    )
    (net (code "143") (name "Net-(IC9A--IN)") (class "Default")
      (node (ref "IC9") (pin "2") (pinfunction "-IN_2") (pintype "input"))
      (node (ref "R47") (pin "1") (pinfunction "1_1") (pintype "passive"))
      (node (ref "R48") (pin "2") (pinfunction "2_2") (pintype "passive"))
    )
    (net (code "144") (name "Net-(IC9A-OUT)") (class "Default")
      (node (ref "IC9") (pin "1") (pinfunction "OUT_1") (pintype "output"))
      (node (ref "R47") (pin "2") (pinfunction "2_2") (pintype "passive"))
      (node (ref "R49") (pin "1") (pinfunction "1_1") (pintype "passive"))
    )
    (net (code "145") (name "Net-(IC9B-+IN)") (class "Default")
      (node (ref "C67") (pin "1") (pinfunction "1_1") (pintype "passive"))
      (node (ref "IC9") (pin "5") (pinfunction "+IN_5") (pintype "input"))
      (node (ref "R51") (pin "2") (pinfunction "2_2") (pintype "passive"))
    )
    (net (code "146") (name "Net-(IC9B--IN)") (class "Default")
      (node (ref "IC9") (pin "6") (pinfunction "-IN_6") (pintype "input"))
      (node (ref "R52") (pin "1") (pinfunction "1_1") (pintype "passive"))
      (node (ref "R53") (pin "2") (pinfunction "2_2") (pintype "passive"))
    )
    (net (code "147") (name "Net-(IC9B-OUT)") (class "Default")
      (node (ref "IC9") (pin "7") (pinfunction "OUT_7") (pintype "output"))
      (node (ref "R36") (pin "1") (pinfunction "1_1") (pintype "passive"))
      (node (ref "R52") (pin "2") (pinfunction "2_2") (pintype "passive"))
    )
    (net (code "148") (name "Net-(IC9C--IN)") (class "Default")
      (node (ref "IC9") (pin "8") (pinfunction "OUT_8") (pintype "output"))
      (node (ref "IC9") (pin "9") (pinfunction "-IN_9") (pintype "input"))
      (node (ref "R37") (pin "1") (pinfunction "1_1") (pintype "passive"))
    )
    (net (code "149") (name "Net-(IC9D--IN)") (class "Default")
      (node (ref "IC9") (pin "13") (pinfunction "-IN_13") (pintype "input"))
      (node (ref "IC9") (pin "14") (pinfunction "OUT_14") (pintype "output"))
      (node (ref "R33") (pin "1") (pinfunction "1_1") (pintype "passive"))
    )
    (net (code "150") (name "Net-(IC10A-+IN)") (class "Default")
      (node (ref "C70") (pin "1") (pinfunction "1_1") (pintype "passive"))
      (node (ref "IC10") (pin "3") (pinfunction "+IN_3") (pintype "input"))
      (node (ref "R57") (pin "1") (pinfunction "1_1") (pintype "passive"))
    )
    (net (code "151") (name "Net-(IC10A--IN)") (class "Default")
      (node (ref "C68") (pin "1") (pinfunction "1_1") (pintype "passive"))
      (node (ref "IC10") (pin "2") (pinfunction "-IN_2") (pintype "input"))
      (node (ref "R56") (pin "1") (pinfunction "1_1") (pintype "passive"))
    )
    (net (code "152") (name "Net-(IC10A-OUT)") (class "Default")
      (node (ref "C68") (pin "2") (pinfunction "2_2") (pintype "passive"))
      (node (ref "IC10") (pin "1") (pinfunction "OUT_1") (pintype "output"))
      (node (ref "R38") (pin "2") (pinfunction "2_2") (pintype "passive"))
      (node (ref "R54") (pin "1") (pinfunction "1_1") (pintype "passive"))
    )
    (net (code "153") (name "Net-(IC10B-+IN)") (class "Default")
      (node (ref "C62") (pin "1") (pinfunction "1_1") (pintype "passive"))
      (node (ref "IC10") (pin "5") (pinfunction "+IN_5") (pintype "input"))
      (node (ref "R40") (pin "1") (pinfunction "1_1") (pintype "passive"))
    )
    (net (code "154") (name "Net-(IC10B--IN)") (class "Default")
      (node (ref "C61") (pin "1") (pinfunction "1_1") (pintype "passive"))
      (node (ref "IC10") (pin "6") (pinfunction "-IN_6") (pintype "input"))
      (node (ref "R39") (pin "1") (pinfunction "1_1") (pintype "passive"))
    )
    (net (code "155") (name "Net-(IC10B-OUT)") (class "Default")
      (node (ref "C61") (pin "2") (pinfunction "2_2") (pintype "passive"))
      (node (ref "IC10") (pin "7") (pinfunction "OUT_7") (pintype "output"))
      (node (ref "R24") (pin "2") (pinfunction "2_2") (pintype "passive"))
      (node (ref "R25") (pin "1") (pinfunction "1_1") (pintype "passive"))
    )
    (net (code "156") (name "Net-(Q1-D)") (class "Default")
      (node (ref "PWR") (pin "1") (pinfunction "1_1") (pintype "passive"))
      (node (ref "PWR") (pin "2") (pinfunction "2_2") (pintype "passive"))
      (node (ref "Q1") (pin "3") (pinfunction "D_3") (pintype "passive"))
    )
    (net (code "157") (name "Net-(Q2-D)") (class "Default")
      (node (ref "PWR") (pin "10") (pinfunction "10_10") (pintype "passive"))
      (node (ref "PWR") (pin "9") (pinfunction "9_9") (pintype "passive"))
      (node (ref "Q2") (pin "3") (pinfunction "D_3") (pintype "passive"))
    )
    (net (code "158") (name "Net-(Q3-B)") (class "Default")
      (node (ref "Q3") (pin "1") (pinfunction "B_1") (pintype "passive"))
      (node (ref "R7") (pin "1") (pinfunction "1_1") (pintype "passive"))
      (node (ref "R8") (pin "2") (pinfunction "2_2") (pintype "passive"))
    )
    (net (code "159") (name "Net-(Q4-B)") (class "Default")
      (node (ref "Q4") (pin "1") (pinfunction "B_1") (pintype "passive"))
      (node (ref "R9") (pin "1") (pinfunction "1_1") (pintype "passive"))
    )
    (net (code "160") (name "Net-(Q4-C)") (class "Default")
      (node (ref "Q4") (pin "3") (pinfunction "C_3") (pintype "passive"))
      (node (ref "R16") (pin "2") (pinfunction "2_2") (pintype "passive"))
      (node (ref "R18") (pin "1") (pinfunction "1_1") (pintype "passive"))
    )
    (net (code "161") (name "Net-(Q5-B)") (class "Default")
      (node (ref "Q5") (pin "1") (pinfunction "B_1") (pintype "passive"))
      (node (ref "R10") (pin "1") (pinfunction "1_1") (pintype "passive"))
    )
    (net (code "162") (name "Net-(Q5-C)") (class "Default")
      (node (ref "Q5") (pin "3") (pinfunction "C_3") (pintype "passive"))
      (node (ref "R21") (pin "1") (pinfunction "1_1") (pintype "passive"))
      (node (ref "R22") (pin "1") (pinfunction "1_1") (pintype "passive"))
    )
    (net (code "163") (name "Net-(Q6-B)") (class "Default")
      (node (ref "Q6") (pin "1") (pinfunction "B_1") (pintype "passive"))
      (node (ref "R12") (pin "1") (pinfunction "1_1") (pintype "passive"))
      (node (ref "R13") (pin "2") (pinfunction "2_2") (pintype "passive"))
    )
    (net (code "164") (name "Net-(X1N-1)") (class "Default")
      (node (ref "R1") (pin "2") (pinfunction "2_2") (pintype "passive"))
      (node (ref "X1") (pin "21") (pinfunction "1_21") (pintype "passive"))
    )
    (net (code "165") (name "unconnected-(IC4A-PB0-Pad46)") (class "Default")
      (node (ref "IC4") (pin "46") (pinfunction "PB0_46") (pintype "bidirectional"))
    )
    (net (code "166") (name "unconnected-(IC4A-PB1-Pad47)") (class "Default")
      (node (ref "IC4") (pin "47") (pinfunction "PB1_47") (pintype "bidirectional"))
    )
    (net (code "167") (name "unconnected-(IC4A-PB2-Pad48)") (class "Default")
      (node (ref "IC4") (pin "48") (pinfunction "PB2_48") (pintype "bidirectional"))
    )
    (net (code "168") (name "unconnected-(IC4A-PC4-Pad44)") (class "Default")
      (node (ref "IC4") (pin "44") (pinfunction "PC4_44") (pintype "bidirectional"))
    )
    (net (code "169") (name "unconnected-(IC4A-PC5-Pad45)") (class "Default")
      (node (ref "IC4") (pin "45") (pinfunction "PC5_45") (pintype "bidirectional"))
    )
    (net (code "170") (name "unconnected-(IC4A-PC14-Pad8)") (class "Default")
      (node (ref "IC4") (pin "8") (pinfunction "PC14_8") (pintype "bidirectional"))
    )
    (net (code "171") (name "unconnected-(IC4A-PC15-Pad9)") (class "Default")
      (node (ref "IC4") (pin "9") (pinfunction "PC15_9") (pintype "bidirectional"))
    )
    (net (code "172") (name "unconnected-(IC4A-VBAT-Pad6)") (class "Default")
      (node (ref "IC4") (pin "6") (pinfunction "VBAT_6") (pintype "bidirectional"))
    )
    (net (code "173") (name "unconnected-(IC4B-PC6-Pad96)") (class "Default")
      (node (ref "IC4") (pin "96") (pinfunction "PC6_96") (pintype "bidirectional"))
    )
    (net (code "174") (name "unconnected-(IC4B-PD11-Pad80)") (class "Default")
      (node (ref "IC4") (pin "80") (pinfunction "PD11_80") (pintype "bidirectional"))
    )
    (net (code "175") (name "unconnected-(IC4B-PD12-Pad81)") (class "Default")
      (node (ref "IC4") (pin "81") (pinfunction "PD12_81") (pintype "bidirectional"))
    )
    (net (code "176") (name "unconnected-(IC4B-PD13-Pad82)") (class "Default")
      (node (ref "IC4") (pin "82") (pinfunction "PD13_82") (pintype "bidirectional"))
    )
    (net (code "177") (name "unconnected-(IC4B-PG2-Pad87)") (class "Default")
      (node (ref "IC4") (pin "87") (pinfunction "PG2_87") (pintype "bidirectional"))
    )
    (net (code "178") (name "unconnected-(IC4B-PG3-Pad88)") (class "Default")
      (node (ref "IC4") (pin "88") (pinfunction "PG3_88") (pintype "bidirectional"))
    )
    (net (code "179") (name "unconnected-(IC4B-PG6-Pad91)") (class "Default")
      (node (ref "IC4") (pin "91") (pinfunction "PG6_91") (pintype "bidirectional"))
    )
    (net (code "180") (name "unconnected-(IC4B-PG7-Pad92)") (class "Default")
      (node (ref "IC4") (pin "92") (pinfunction "PG7_92") (pintype "bidirectional"))
    )
    (net (code "181") (name "unconnected-(IC4C-PA8-Pad100)") (class "Default")
      (node (ref "IC4") (pin "100") (pinfunction "PA8_100") (pintype "bidirectional"))
    )
    (net (code "182") (name "unconnected-(IC4C-PB9-Pad140)") (class "Default")
      (node (ref "IC4") (pin "140") (pinfunction "PB9_140") (pintype "bidirectional"))
    )
    (net (code "183") (name "unconnected-(IC4C-PC7-Pad97)") (class "Default")
      (node (ref "IC4") (pin "97") (pinfunction "PC7_97") (pintype "bidirectional"))
    )
    (net (code "184") (name "unconnected-(IC4C-PC8-Pad98)") (class "Default")
      (node (ref "IC4") (pin "98") (pinfunction "PC8_98") (pintype "bidirectional"))
    )
    (net (code "185") (name "unconnected-(IC4C-PD5-Pad119)") (class "Default")
      (node (ref "IC4") (pin "119") (pinfunction "PD5_119") (pintype "bidirectional"))
    )
    (net (code "186") (name "unconnected-(IC4C-PD7-Pad123)") (class "Default")
      (node (ref "IC4") (pin "123") (pinfunction "PD7_123") (pintype "bidirectional"))
    )
    (net (code "187") (name "unconnected-(IC4C-PG11-Pad126)") (class "Default")
      (node (ref "IC4") (pin "126") (pinfunction "PG11_126") (pintype "bidirectional"))
    )
    (net (code "188") (name "unconnected-(IC4C-PG12-Pad127)") (class "Default")
      (node (ref "IC4") (pin "127") (pinfunction "PG12_127") (pintype "bidirectional"))
    )
    (net (code "189") (name "unconnected-(IC4C-PG13-Pad128)") (class "Default")
      (node (ref "IC4") (pin "128") (pinfunction "PG13_128") (pintype "bidirectional"))
    )
    (net (code "190") (name "unconnected-(IC6-MCLK-Pad3)") (class "Default")
      (node (ref "IC6") (pin "3") (pinfunction "MCLK_3") (pintype "bidirectional"))
    )
    (net (code "191") (name "unconnected-(IC6-~{AMUTEC}-Pad23)") (class "Default")
      (node (ref "IC6") (pin "23") (pinfunction "~{AMUTEC}_23") (pintype "bidirectional"))
    )
    (net (code "192") (name "unconnected-(IC6-~{BMUTEC}-Pad28)") (class "Default")
      (node (ref "IC6") (pin "28") (pinfunction "~{BMUTEC}_28") (pintype "bidirectional"))
    )
    (net (code "193") (name "unconnected-(X1G-1-Pad15)") (class "Default")
      (node (ref "X1") (pin "15") (pinfunction "1_15") (pintype "passive"))
    )
    (net (code "194") (name "unconnected-(X1S-1-Pad4)") (class "Default")
      (node (ref "X1") (pin "4") (pinfunction "1_4") (pintype "passive"))
    )
  )
)
